# canSlaveV04.net
KiCad netlist of a schematic drawn in EAGLE
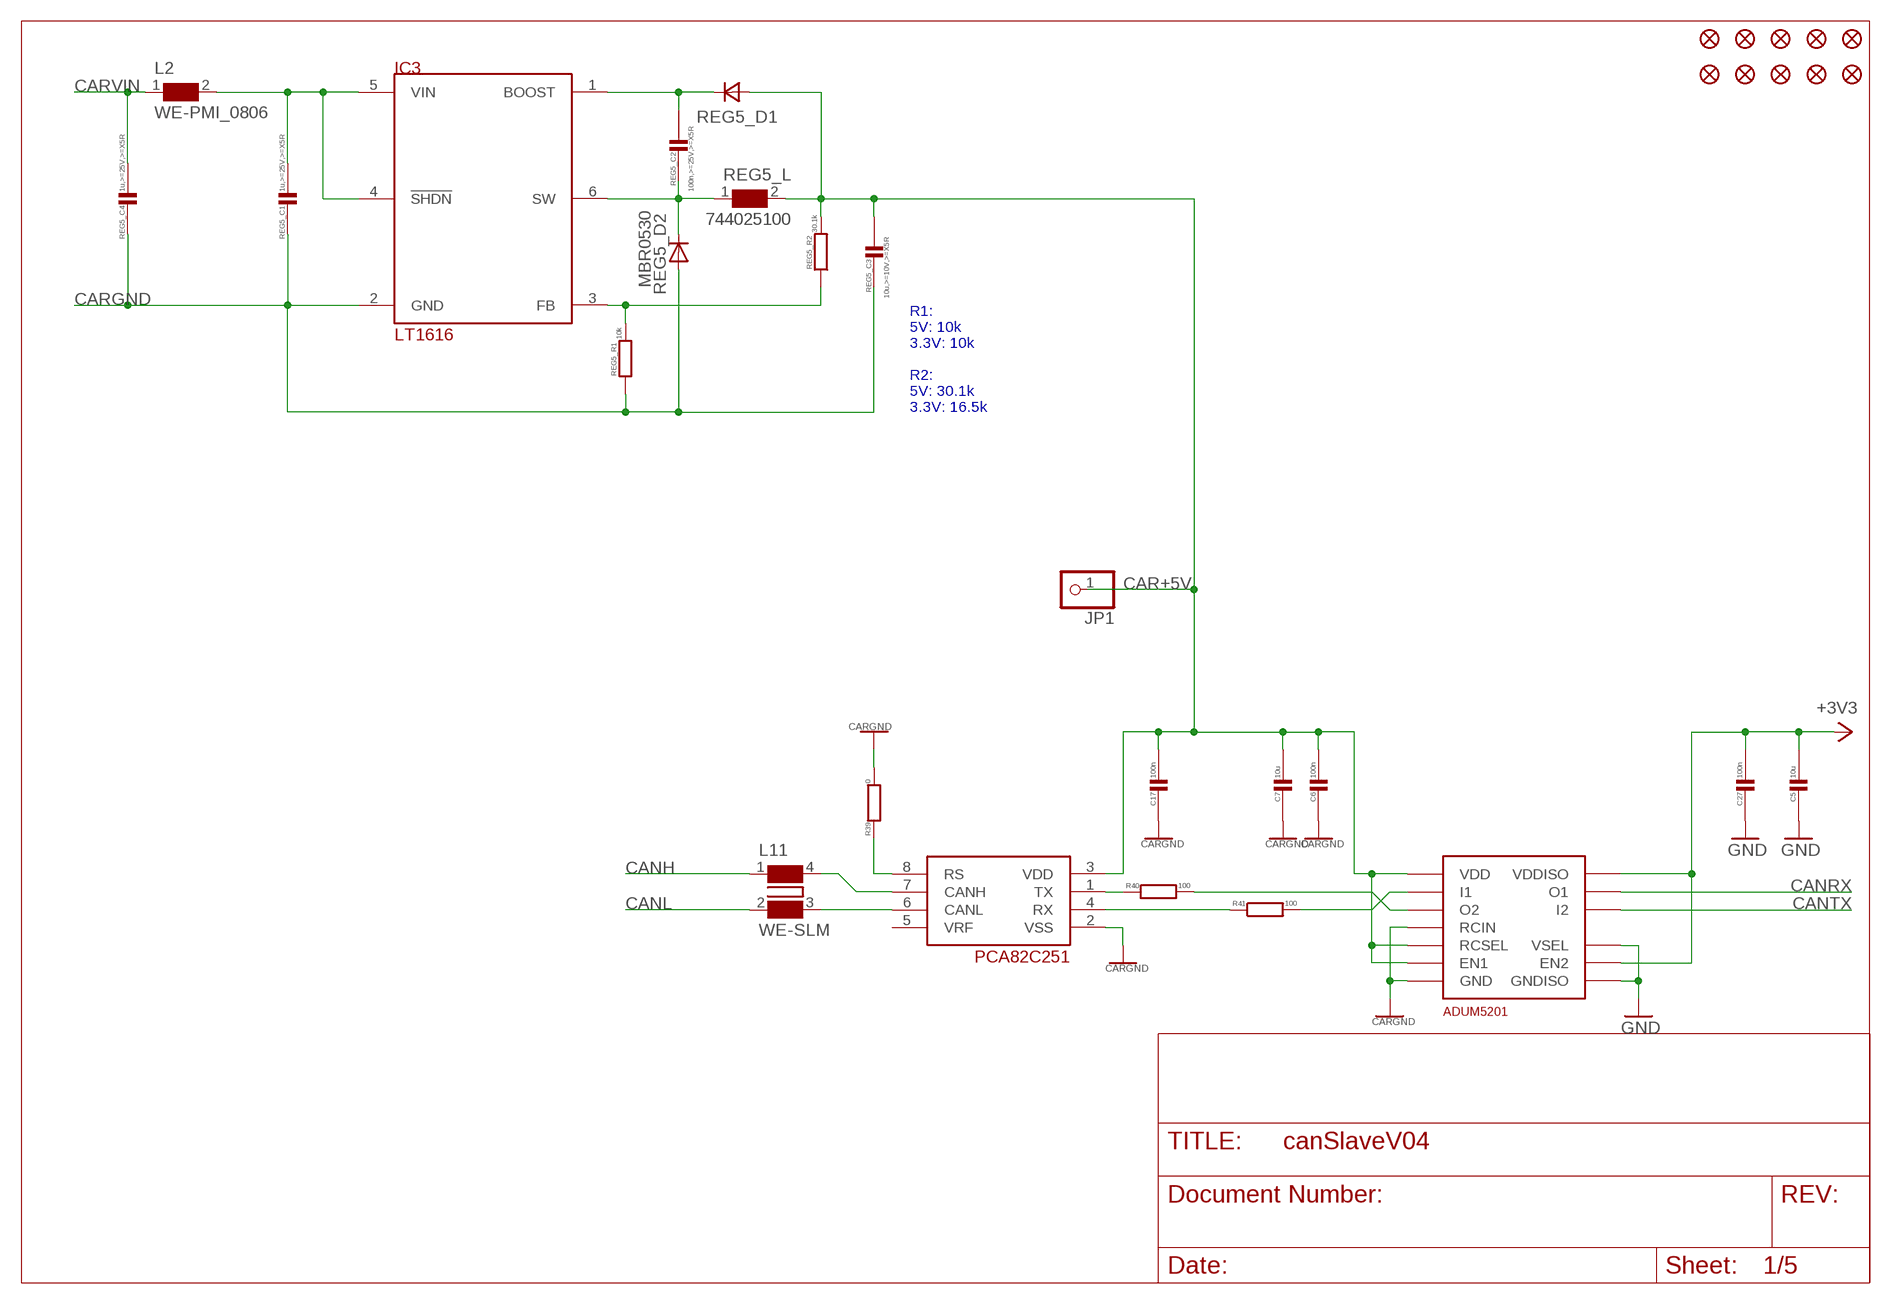
[diagram p0: schematic, sheet 1]
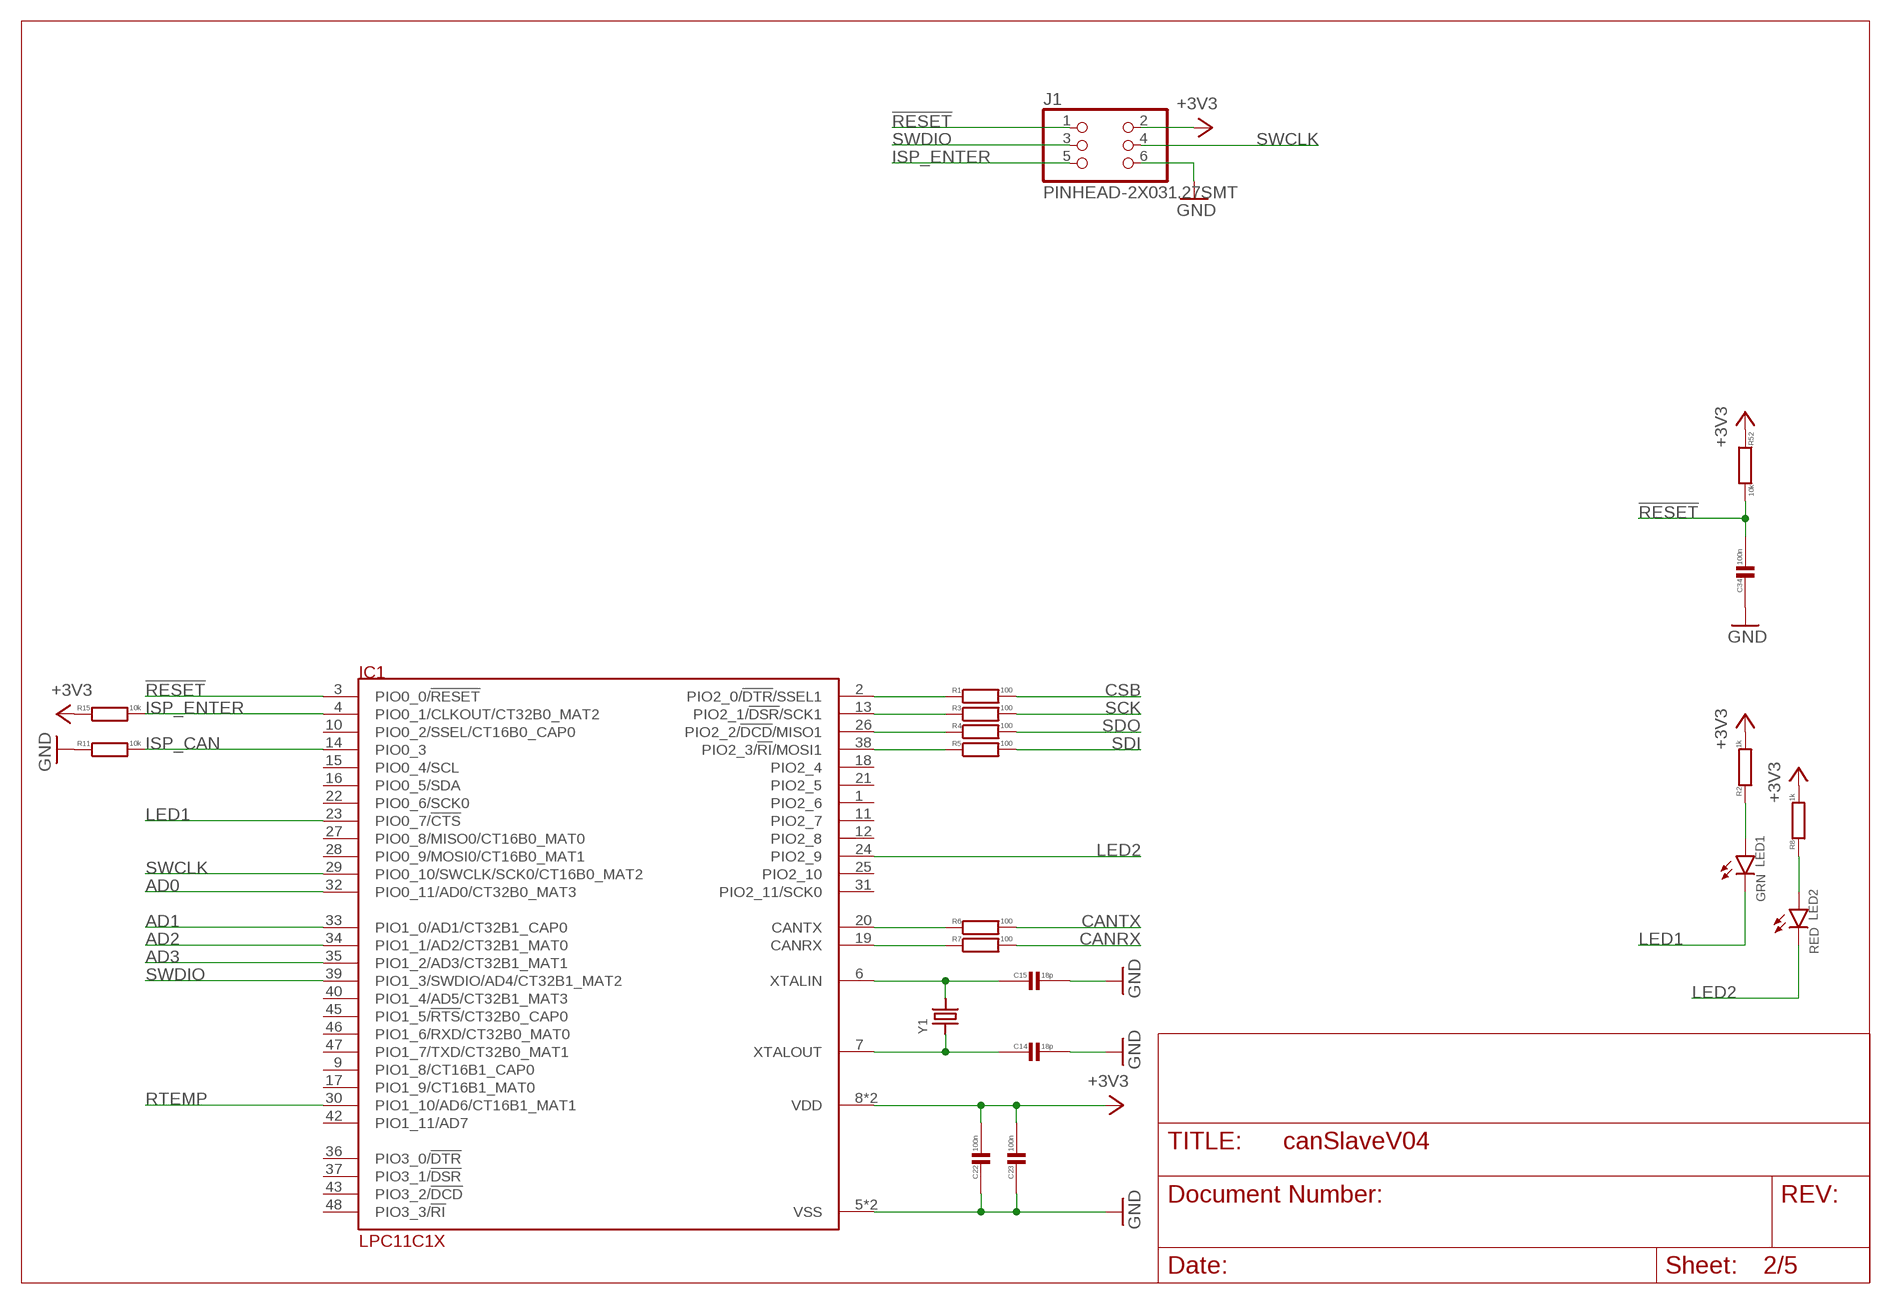
[diagram p1: schematic, sheet 2]
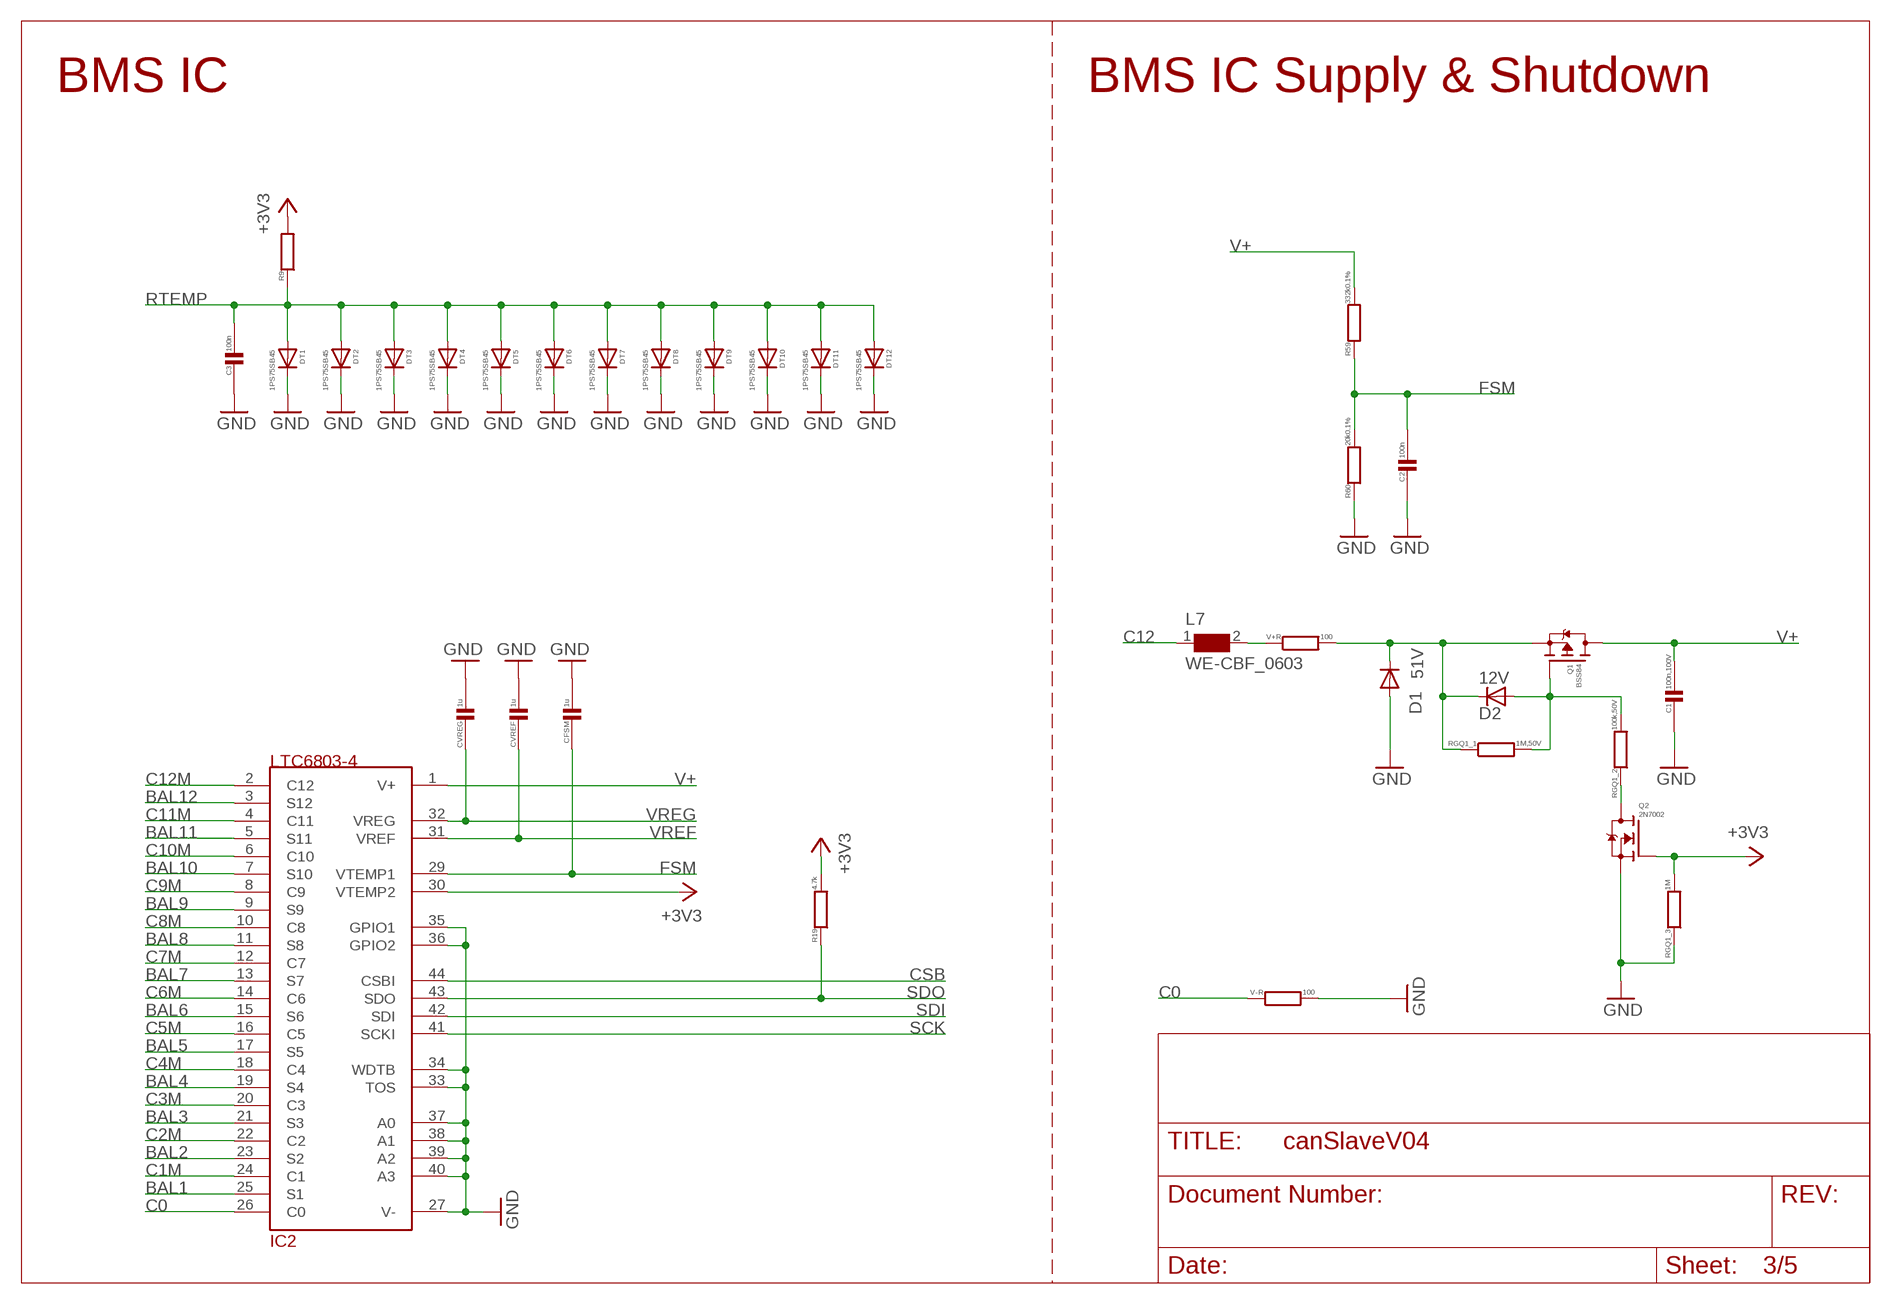
[diagram p2: schematic, sheet 3]
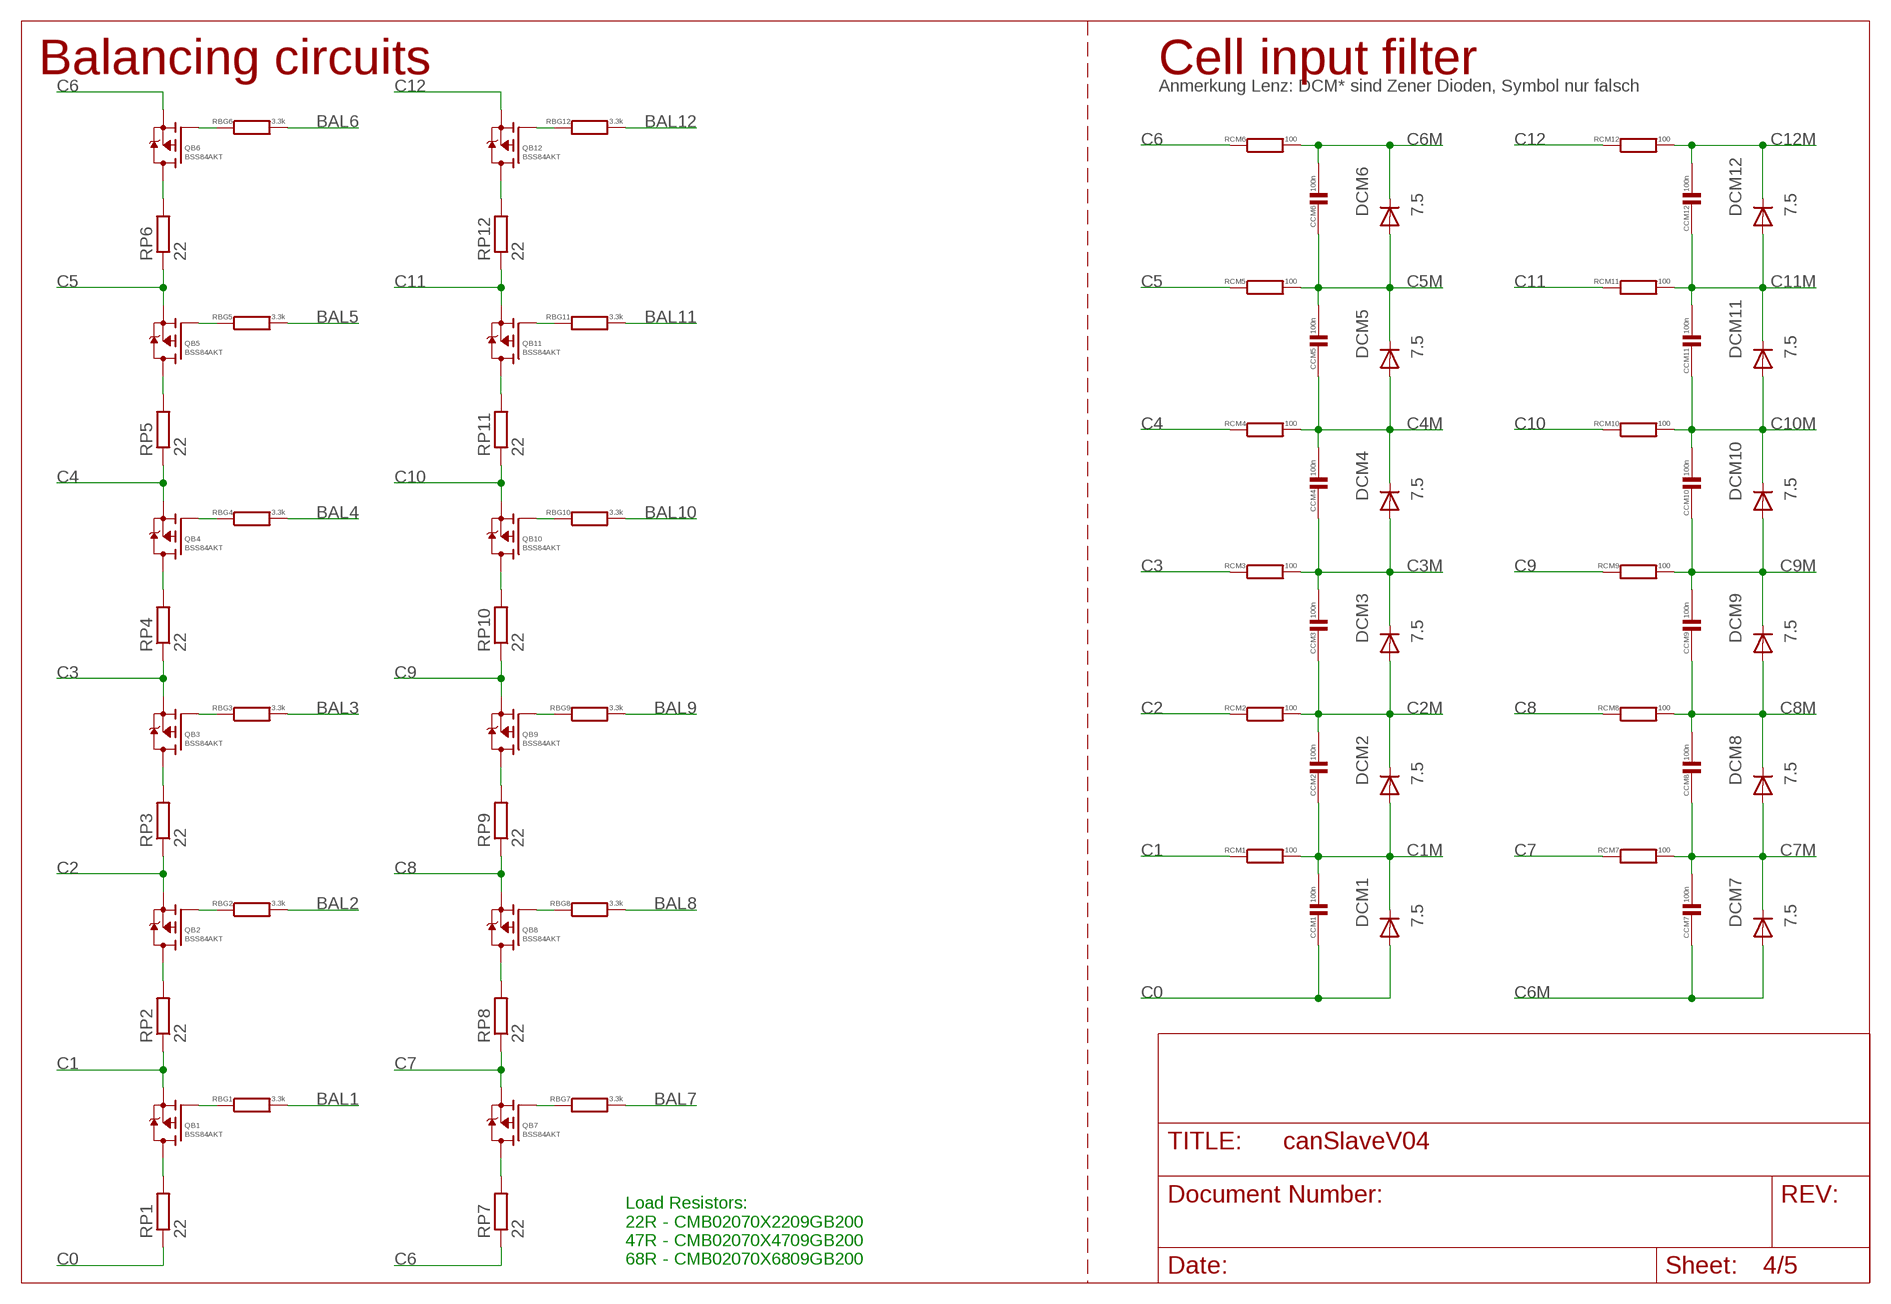
[diagram p3: schematic, sheet 4]
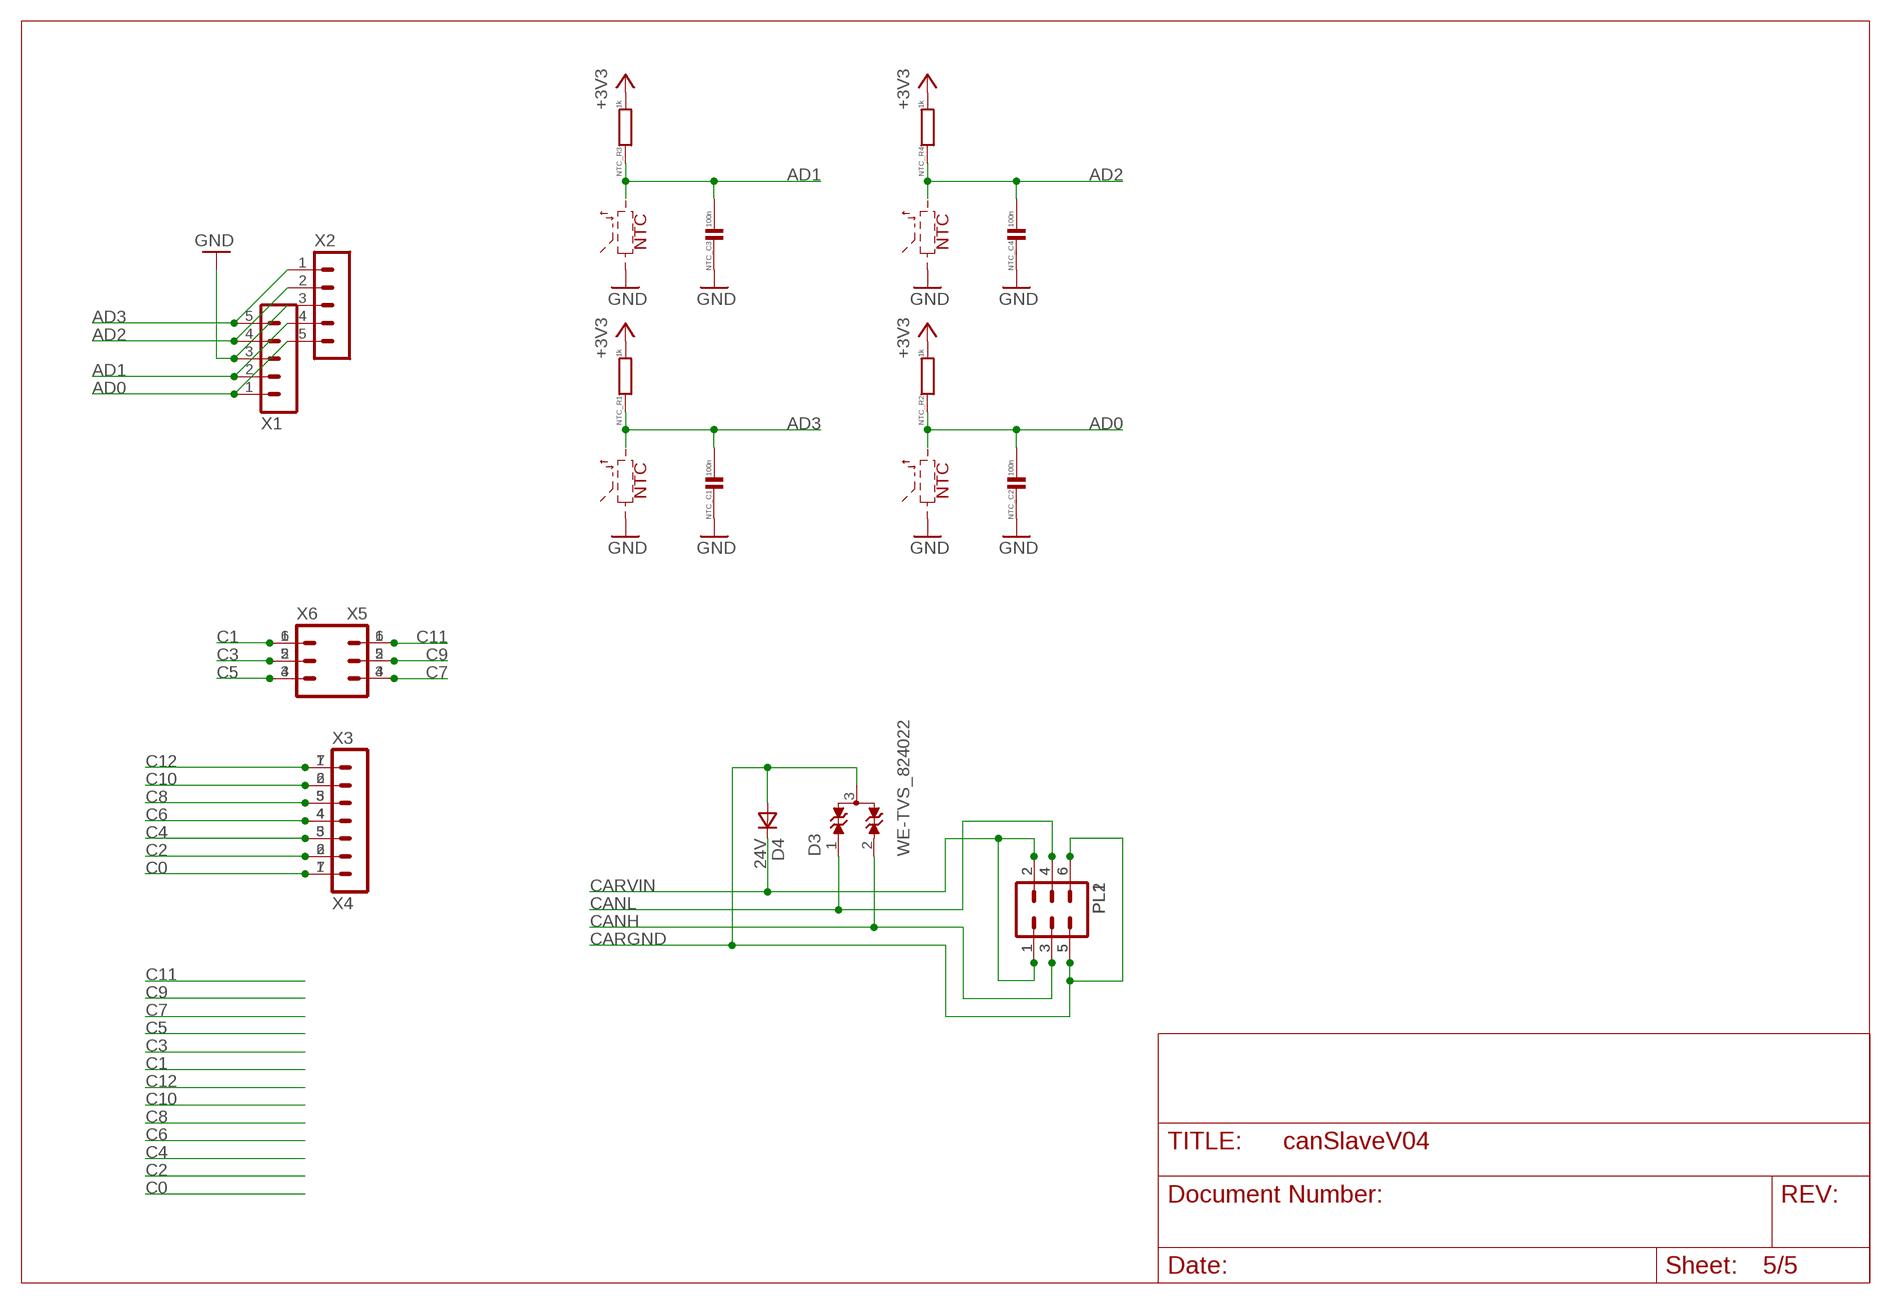
[diagram p4: schematic, sheet 5]

(export (version "E")
  (design (tool "Eeschema 10.0.6"))
  (components
    (comp (ref "D3")
      (value "WE-TVS_824022")
      (footprint "eagle-import:WE-TVS_SOT23-3L")
      (libsource (lib "eagle-import") (part "WE-TVS_824022"))
    )
    (comp (ref "D4")
      (value "24V")
      (footprint "eagle-import:SOD323")
      (fields (field (name "MPN") "CDSOD323-T05C"))
      (libsource (lib "eagle-import") (part "DSOD323"))
    )
    (comp (ref "NTC_C1")
      (value "100n")
      (footprint "eagle-import:C0402")
      (libsource (lib "eagle-import") (part "C0402"))
    )
    (comp (ref "NTC_C2")
      (value "100n")
      (footprint "eagle-import:C0402")
      (libsource (lib "eagle-import") (part "C0402"))
    )
    (comp (ref "NTC_C3")
      (value "100n")
      (footprint "eagle-import:C0402")
      (libsource (lib "eagle-import") (part "C0402"))
    )
    (comp (ref "NTC_C4")
      (value "100n")
      (footprint "eagle-import:C0402")
      (libsource (lib "eagle-import") (part "C0402"))
    )
    (comp (ref "NTC_R1")
      (value "1k")
      (footprint "eagle-import:R0402")
      (libsource (lib "eagle-import") (part "R0402"))
    )
    (comp (ref "NTC_R2")
      (value "1k")
      (footprint "eagle-import:R0402")
      (libsource (lib "eagle-import") (part "R0402"))
    )
    (comp (ref "NTC_R3")
      (value "1k")
      (footprint "eagle-import:R0402")
      (libsource (lib "eagle-import") (part "R0402"))
    )
    (comp (ref "NTC_R4")
      (value "1k")
      (footprint "eagle-import:R0402")
      (libsource (lib "eagle-import") (part "R0402"))
    )
    (comp (ref "PL1")
      (value "06V")
      (footprint "eagle-import:06V")
      (libsource (lib "eagle-import") (part "06V"))
    )
    (comp (ref "PL2")
      (value "06H")
      (footprint "eagle-import:06H")
      (libsource (lib "eagle-import") (part "06H"))
    )
    (comp (ref "X1")
      (value "HEADER_POS5_43650-0500")
      (footprint "eagle-import:43650-0500")
      (libsource (lib "eagle-import") (part "HEADER_POS5_?43650-0500"))
    )
    (comp (ref "X2")
      (value "HEADER_POS5_43650-0515")
      (footprint "eagle-import:43650-0515")
      (libsource (lib "eagle-import") (part "HEADER_POS5_?43650-0515"))
    )
    (comp (ref "X3")
      (value "HEADER_POS7_43650-0700")
      (footprint "eagle-import:43650-0700")
      (libsource (lib "eagle-import") (part "HEADER_POS7_?43650-0700"))
    )
    (comp (ref "X4")
      (value "HEADER_POS7_43650-0715")
      (footprint "eagle-import:43650-0715")
      (libsource (lib "eagle-import") (part "HEADER_POS7_?43650-0715"))
    )
    (comp (ref "X5")
      (value "HEADER_POS6_43650-0615")
      (footprint "eagle-import:43650-0615")
      (libsource (lib "eagle-import") (part "HEADER_POS6_?43650-0615"))
    )
    (comp (ref "X6")
      (value "HEADER_POS6_43650-0600")
      (footprint "eagle-import:43650-0600")
      (libsource (lib "eagle-import") (part "HEADER_POS6_?43650-0600"))
    )
    (comp (ref "C1")
      (value "100n,100V")
      (footprint "eagle-import:C0603")
      (libsource (lib "eagle-import") (part "C0603"))
    )
    (comp (ref "C2")
      (value "100n")
      (footprint "eagle-import:C0402")
      (libsource (lib "eagle-import") (part "C0402"))
    )
    (comp (ref "C3")
      (value "100n")
      (footprint "eagle-import:C0402")
      (libsource (lib "eagle-import") (part "C0402"))
    )
    (comp (ref "CFSM")
      (value "1u")
      (footprint "eagle-import:C0402")
      (libsource (lib "eagle-import") (part "C0402"))
    )
    (comp (ref "CVREF")
      (value "1u")
      (footprint "eagle-import:C0402")
      (libsource (lib "eagle-import") (part "C0402"))
    )
    (comp (ref "CVREG")
      (value "1u")
      (footprint "eagle-import:C0402")
      (libsource (lib "eagle-import") (part "C0402"))
    )
    (comp (ref "D1")
      (value "51V")
      (footprint "eagle-import:SOD323-R")
      (libsource (lib "eagle-import") (part "DIODE-SOD323-R"))
    )
    (comp (ref "D2")
      (value "12V")
      (footprint "eagle-import:SOD323-R")
      (libsource (lib "eagle-import") (part "DIODE-SOD323-R"))
    )
    (comp (ref "DT1")
      (value "1PS75SB45")
      (footprint "eagle-import:SOT416")
      (libsource (lib "eagle-import") (part "DIODE-SOT416"))
    )
    (comp (ref "DT2")
      (value "1PS75SB45")
      (footprint "eagle-import:SOT416")
      (libsource (lib "eagle-import") (part "DIODE-SOT416"))
    )
    (comp (ref "DT3")
      (value "1PS75SB45")
      (footprint "eagle-import:SOT416")
      (libsource (lib "eagle-import") (part "DIODE-SOT416"))
    )
    (comp (ref "DT4")
      (value "1PS75SB45")
      (footprint "eagle-import:SOT416")
      (libsource (lib "eagle-import") (part "DIODE-SOT416"))
    )
    (comp (ref "DT5")
      (value "1PS75SB45")
      (footprint "eagle-import:SOT416")
      (libsource (lib "eagle-import") (part "DIODE-SOT416"))
    )
    (comp (ref "DT6")
      (value "1PS75SB45")
      (footprint "eagle-import:SOT416")
      (libsource (lib "eagle-import") (part "DIODE-SOT416"))
    )
    (comp (ref "DT7")
      (value "1PS75SB45")
      (footprint "eagle-import:SOT416")
      (libsource (lib "eagle-import") (part "DIODE-SOT416"))
    )
    (comp (ref "DT8")
      (value "1PS75SB45")
      (footprint "eagle-import:SOT416")
      (libsource (lib "eagle-import") (part "DIODE-SOT416"))
    )
    (comp (ref "DT9")
      (value "1PS75SB45")
      (footprint "eagle-import:SOT416")
      (libsource (lib "eagle-import") (part "DIODE-SOT416"))
    )
    (comp (ref "DT10")
      (value "1PS75SB45")
      (footprint "eagle-import:SOT416")
      (libsource (lib "eagle-import") (part "DIODE-SOT416"))
    )
    (comp (ref "DT11")
      (value "1PS75SB45")
      (footprint "eagle-import:SOT416")
      (libsource (lib "eagle-import") (part "DIODE-SOT416"))
    )
    (comp (ref "DT12")
      (value "1PS75SB45")
      (footprint "eagle-import:SOT416")
      (libsource (lib "eagle-import") (part "DIODE-SOT416"))
    )
    (comp (ref "IC2")
      (value "LTC6803-4")
      (footprint "eagle-import:44SSOP")
      (libsource (lib "eagle-import") (part "LTC6803-4"))
    )
    (comp (ref "L7")
      (value "WE-CBF_0603")
      (footprint "eagle-import:0603")
      (libsource (lib "eagle-import") (part "WE-CBF_0603"))
    )
    (comp (ref "Q1")
      (value "BSS84")
      (footprint "eagle-import:SOT23")
      (libsource (lib "eagle-import") (part "BSS84"))
    )
    (comp (ref "Q2")
      (value "2N7002")
      (footprint "eagle-import:SOT23")
      (libsource (lib "eagle-import") (part "2N7002"))
    )
    (comp (ref "R9")
      (value "R0603")
      (footprint "eagle-import:R0603")
      (libsource (lib "eagle-import") (part "R0603"))
    )
    (comp (ref "R19")
      (value "4.7k")
      (footprint "eagle-import:R0402")
      (libsource (lib "eagle-import") (part "R0402"))
    )
    (comp (ref "R59")
      (value "332k0.1%")
      (footprint "eagle-import:R0603")
      (libsource (lib "eagle-import") (part "R0603"))
    )
    (comp (ref "R60")
      (value "20k0.1%")
      (footprint "eagle-import:R0402")
      (libsource (lib "eagle-import") (part "R0402"))
    )
    (comp (ref "RGQ1_1")
      (value "1M,50V")
      (footprint "eagle-import:R0603")
      (libsource (lib "eagle-import") (part "R0603"))
    )
    (comp (ref "RGQ1_2")
      (value "100k,50V")
      (footprint "eagle-import:R0603")
      (libsource (lib "eagle-import") (part "R0603"))
    )
    (comp (ref "RGQ1_3")
      (value "1M")
      (footprint "eagle-import:R0402")
      (libsource (lib "eagle-import") (part "R0402"))
    )
    (comp (ref "V+R")
      (value "100")
      (footprint "eagle-import:R0603")
      (libsource (lib "eagle-import") (part "R0603"))
    )
    (comp (ref "V-R")
      (value "100")
      (footprint "eagle-import:R0603")
      (libsource (lib "eagle-import") (part "R0603"))
    )
    (comp (ref "C14")
      (value "18p")
      (footprint "eagle-import:C0402")
      (libsource (lib "eagle-import") (part "C0402"))
    )
    (comp (ref "C15")
      (value "18p")
      (footprint "eagle-import:C0402")
      (libsource (lib "eagle-import") (part "C0402"))
    )
    (comp (ref "C22")
      (value "100n")
      (footprint "eagle-import:C0402")
      (libsource (lib "eagle-import") (part "C0402"))
    )
    (comp (ref "C23")
      (value "100n")
      (footprint "eagle-import:C0402")
      (libsource (lib "eagle-import") (part "C0402"))
    )
    (comp (ref "C34")
      (value "100n")
      (footprint "eagle-import:C0402")
      (libsource (lib "eagle-import") (part "C0402"))
    )
    (comp (ref "IC1")
      (value "LPC11C1X")
      (footprint "eagle-import:LQFP48")
      (libsource (lib "eagle-import") (part "LPC11C1X"))
    )
    (comp (ref "J1")
      (value "PINHEAD-2X031.27SMT")
      (footprint "eagle-import:2X03_1.27MM_SMT")
      (libsource (lib "eagle-import") (part "PINHEAD-2X031.27SMT"))
    )
    (comp (ref "LED1")
      (value "GRN")
      (footprint "eagle-import:CHIPLED_0402")
      (libsource (lib "eagle-import") (part "LED0402"))
    )
    (comp (ref "LED2")
      (value "RED")
      (footprint "eagle-import:CHIPLED_0402")
      (libsource (lib "eagle-import") (part "LED0402"))
    )
    (comp (ref "R1")
      (value "100")
      (footprint "eagle-import:R0402")
      (libsource (lib "eagle-import") (part "R0402"))
    )
    (comp (ref "R2")
      (value "1k")
      (footprint "eagle-import:R0402")
      (libsource (lib "eagle-import") (part "R0402"))
    )
    (comp (ref "R3")
      (value "100")
      (footprint "eagle-import:R0402")
      (libsource (lib "eagle-import") (part "R0402"))
    )
    (comp (ref "R4")
      (value "100")
      (footprint "eagle-import:R0402")
      (libsource (lib "eagle-import") (part "R0402"))
    )
    (comp (ref "R5")
      (value "100")
      (footprint "eagle-import:R0402")
      (libsource (lib "eagle-import") (part "R0402"))
    )
    (comp (ref "R6")
      (value "100")
      (footprint "eagle-import:R0402")
      (libsource (lib "eagle-import") (part "R0402"))
    )
    (comp (ref "R7")
      (value "100")
      (footprint "eagle-import:R0402")
      (libsource (lib "eagle-import") (part "R0402"))
    )
    (comp (ref "R8")
      (value "1k")
      (footprint "eagle-import:R0402")
      (libsource (lib "eagle-import") (part "R0402"))
    )
    (comp (ref "R11")
      (value "10k")
      (footprint "eagle-import:R0402")
      (libsource (lib "eagle-import") (part "R0402"))
    )
    (comp (ref "R15")
      (value "10k")
      (footprint "eagle-import:R0402")
      (libsource (lib "eagle-import") (part "R0402"))
    )
    (comp (ref "R52")
      (value "10k")
      (footprint "eagle-import:R0402")
      (libsource (lib "eagle-import") (part "R0402"))
    )
    (comp (ref "Y1")
      (value "CRYSTALTHIN")
      (footprint "eagle-import:CRYSTAL_3.2X2.5")
      (libsource (lib "eagle-import") (part "CRYSTALTHIN"))
    )
    (comp (ref "C5")
      (value "10u")
      (footprint "eagle-import:C0603")
      (libsource (lib "eagle-import") (part "C0603"))
    )
    (comp (ref "C6")
      (value "100n")
      (footprint "eagle-import:C0402")
      (libsource (lib "eagle-import") (part "C0402"))
    )
    (comp (ref "C7")
      (value "10u")
      (footprint "eagle-import:C0603")
      (libsource (lib "eagle-import") (part "C0603"))
    )
    (comp (ref "C17")
      (value "100n")
      (footprint "eagle-import:C0402")
      (libsource (lib "eagle-import") (part "C0402"))
    )
    (comp (ref "C27")
      (value "100n")
      (footprint "eagle-import:C0402")
      (libsource (lib "eagle-import") (part "C0402"))
    )
    (comp (ref "FID1")
      (value "FIDUCIAL\"\"")
      (footprint "eagle-import:FIDUCIAL_1MM")
      (libsource (lib "eagle-import") (part "FIDUCIAL{dblquote}{dblquote}"))
    )
    (comp (ref "FID2")
      (value "FIDUCIAL\"\"")
      (footprint "eagle-import:FIDUCIAL_1MM")
      (libsource (lib "eagle-import") (part "FIDUCIAL{dblquote}{dblquote}"))
    )
    (comp (ref "FID3")
      (value "FIDUCIAL\"\"")
      (footprint "eagle-import:FIDUCIAL_1MM")
      (libsource (lib "eagle-import") (part "FIDUCIAL{dblquote}{dblquote}"))
    )
    (comp (ref "FID4")
      (value "FIDUCIAL\"\"")
      (footprint "eagle-import:FIDUCIAL_1MM")
      (libsource (lib "eagle-import") (part "FIDUCIAL{dblquote}{dblquote}"))
    )
    (comp (ref "FID5")
      (value "FIDUCIAL\"\"")
      (footprint "eagle-import:FIDUCIAL_1MM")
      (libsource (lib "eagle-import") (part "FIDUCIAL{dblquote}{dblquote}"))
    )
    (comp (ref "FID6")
      (value "FIDUCIAL\"\"")
      (footprint "eagle-import:FIDUCIAL_1MM")
      (libsource (lib "eagle-import") (part "FIDUCIAL{dblquote}{dblquote}"))
    )
    (comp (ref "FID7")
      (value "FIDUCIAL\"\"")
      (footprint "eagle-import:FIDUCIAL_1MM")
      (libsource (lib "eagle-import") (part "FIDUCIAL{dblquote}{dblquote}"))
    )
    (comp (ref "FID8")
      (value "FIDUCIAL\"\"")
      (footprint "eagle-import:FIDUCIAL_1MM")
      (libsource (lib "eagle-import") (part "FIDUCIAL{dblquote}{dblquote}"))
    )
    (comp (ref "FID9")
      (value "FIDUCIAL\"\"")
      (footprint "eagle-import:FIDUCIAL_1MM")
      (libsource (lib "eagle-import") (part "FIDUCIAL{dblquote}{dblquote}"))
    )
    (comp (ref "FID10")
      (value "FIDUCIAL\"\"")
      (footprint "eagle-import:FIDUCIAL_1MM")
      (libsource (lib "eagle-import") (part "FIDUCIAL{dblquote}{dblquote}"))
    )
    (comp (ref "IC3")
      (value "LT1616")
      (footprint "eagle-import:SOT23-6")
      (libsource (lib "eagle-import") (part "LT1616"))
    )
    (comp (ref "IC5")
      (value "PCA82C251")
      (footprint "eagle-import:SO-8")
      (libsource (lib "eagle-import") (part "MCP2551"))
    )
    (comp (ref "JP1")
      (value "PINHD-1X1")
      (footprint "eagle-import:1X01")
      (libsource (lib "eagle-import") (part "PINHD-1X1"))
    )
    (comp (ref "L2")
      (value "WE-PMI_0806")
      (footprint "eagle-import:WE-PMI_0806")
      (libsource (lib "eagle-import") (part "WE-PMI_0806"))
    )
    (comp (ref "L11")
      (value "WE-SLM")
      (footprint "eagle-import:WE-SLM")
      (libsource (lib "eagle-import") (part "WE-SLM"))
    )
    (comp (ref "R39")
      (value "0")
      (footprint "eagle-import:R0402")
      (libsource (lib "eagle-import") (part "R0402"))
    )
    (comp (ref "R40")
      (value "100")
      (footprint "eagle-import:R0402")
      (libsource (lib "eagle-import") (part "R0402"))
    )
    (comp (ref "R41")
      (value "100")
      (footprint "eagle-import:R0402")
      (libsource (lib "eagle-import") (part "R0402"))
    )
    (comp (ref "REG5_C1")
      (value "1u,>=25V,>=X5R")
      (footprint "eagle-import:C0603")
      (libsource (lib "eagle-import") (part "C0603"))
    )
    (comp (ref "REG5_C2")
      (value "100n,>=25V,>=X5R")
      (footprint "eagle-import:C0402")
      (libsource (lib "eagle-import") (part "C0402"))
    )
    (comp (ref "REG5_C3")
      (value "10u,>=10V,>=X5R")
      (footprint "eagle-import:C0603")
      (libsource (lib "eagle-import") (part "C0603"))
    )
    (comp (ref "REG5_C4")
      (value "1u,>=25V,>=X5R")
      (footprint "eagle-import:C0603")
      (libsource (lib "eagle-import") (part "C0603"))
    )
    (comp (ref "REG5_D1")
      (value "DSOD323")
      (footprint "eagle-import:SOD323")
      (fields (field (name "MPN") "CDSOD323-T05C"))
      (libsource (lib "eagle-import") (part "DSOD323"))
    )
    (comp (ref "REG5_D2")
      (value "MBR0530")
      (footprint "eagle-import:SOD123")
      (libsource (lib "eagle-import") (part "D-SOD123"))
    )
    (comp (ref "REG5_L")
      (value "744025100")
      (footprint "eagle-import:WE-TPC_2828")
      (libsource (lib "eagle-import") (part "WE-TPC_2828"))
    )
    (comp (ref "REG5_R1")
      (value "10k")
      (footprint "eagle-import:R0402")
      (libsource (lib "eagle-import") (part "R0402"))
    )
    (comp (ref "REG5_R2")
      (value "30.1k")
      (footprint "eagle-import:R0402")
      (libsource (lib "eagle-import") (part "R0402"))
    )
    (comp (ref "U$2")
      (value "ADUM5201")
      (footprint "eagle-import:SO16WB")
      (libsource (lib "eagle-import") (part "ADUM5201"))
    )
    (comp (ref "CCM1")
      (value "100n")
      (footprint "eagle-import:C0402")
      (libsource (lib "eagle-import") (part "C0402"))
    )
    (comp (ref "CCM2")
      (value "100n")
      (footprint "eagle-import:C0402")
      (libsource (lib "eagle-import") (part "C0402"))
    )
    (comp (ref "CCM3")
      (value "100n")
      (footprint "eagle-import:C0402")
      (libsource (lib "eagle-import") (part "C0402"))
    )
    (comp (ref "CCM4")
      (value "100n")
      (footprint "eagle-import:C0402")
      (libsource (lib "eagle-import") (part "C0402"))
    )
    (comp (ref "CCM5")
      (value "100n")
      (footprint "eagle-import:C0402")
      (libsource (lib "eagle-import") (part "C0402"))
    )
    (comp (ref "CCM6")
      (value "100n")
      (footprint "eagle-import:C0402")
      (libsource (lib "eagle-import") (part "C0402"))
    )
    (comp (ref "CCM7")
      (value "100n")
      (footprint "eagle-import:C0402")
      (libsource (lib "eagle-import") (part "C0402"))
    )
    (comp (ref "CCM8")
      (value "100n")
      (footprint "eagle-import:C0402")
      (libsource (lib "eagle-import") (part "C0402"))
    )
    (comp (ref "CCM9")
      (value "100n")
      (footprint "eagle-import:C0402")
      (libsource (lib "eagle-import") (part "C0402"))
    )
    (comp (ref "CCM10")
      (value "100n")
      (footprint "eagle-import:C0402")
      (libsource (lib "eagle-import") (part "C0402"))
    )
    (comp (ref "CCM11")
      (value "100n")
      (footprint "eagle-import:C0402")
      (libsource (lib "eagle-import") (part "C0402"))
    )
    (comp (ref "CCM12")
      (value "100n")
      (footprint "eagle-import:C0402")
      (libsource (lib "eagle-import") (part "C0402"))
    )
    (comp (ref "DCM1")
      (value "7.5")
      (footprint "eagle-import:SOD323-L")
      (libsource (lib "eagle-import") (part "DIODE-SOD323-L"))
    )
    (comp (ref "DCM2")
      (value "7.5")
      (footprint "eagle-import:SOD323-L")
      (libsource (lib "eagle-import") (part "DIODE-SOD323-L"))
    )
    (comp (ref "DCM3")
      (value "7.5")
      (footprint "eagle-import:SOD323-L")
      (libsource (lib "eagle-import") (part "DIODE-SOD323-L"))
    )
    (comp (ref "DCM4")
      (value "7.5")
      (footprint "eagle-import:SOD323-L")
      (libsource (lib "eagle-import") (part "DIODE-SOD323-L"))
    )
    (comp (ref "DCM5")
      (value "7.5")
      (footprint "eagle-import:SOD323-L")
      (libsource (lib "eagle-import") (part "DIODE-SOD323-L"))
    )
    (comp (ref "DCM6")
      (value "7.5")
      (footprint "eagle-import:SOD323-L")
      (libsource (lib "eagle-import") (part "DIODE-SOD323-L"))
    )
    (comp (ref "DCM7")
      (value "7.5")
      (footprint "eagle-import:SOD323-L")
      (libsource (lib "eagle-import") (part "DIODE-SOD323-L"))
    )
    (comp (ref "DCM8")
      (value "7.5")
      (footprint "eagle-import:SOD323-L")
      (libsource (lib "eagle-import") (part "DIODE-SOD323-L"))
    )
    (comp (ref "DCM9")
      (value "7.5")
      (footprint "eagle-import:SOD323-L")
      (libsource (lib "eagle-import") (part "DIODE-SOD323-L"))
    )
    (comp (ref "DCM10")
      (value "7.5")
      (footprint "eagle-import:SOD323-L")
      (libsource (lib "eagle-import") (part "DIODE-SOD323-L"))
    )
    (comp (ref "DCM11")
      (value "7.5")
      (footprint "eagle-import:SOD323-L")
      (libsource (lib "eagle-import") (part "DIODE-SOD323-L"))
    )
    (comp (ref "DCM12")
      (value "7.5")
      (footprint "eagle-import:SOD323-L")
      (libsource (lib "eagle-import") (part "DIODE-SOD323-L"))
    )
    (comp (ref "QB1")
      (value "BSS84AKT")
      (footprint "eagle-import:SOT416")
      (libsource (lib "eagle-import") (part "BSS84AKT"))
    )
    (comp (ref "QB2")
      (value "BSS84AKT")
      (footprint "eagle-import:SOT416")
      (libsource (lib "eagle-import") (part "BSS84AKT"))
    )
    (comp (ref "QB3")
      (value "BSS84AKT")
      (footprint "eagle-import:SOT416")
      (libsource (lib "eagle-import") (part "BSS84AKT"))
    )
    (comp (ref "QB4")
      (value "BSS84AKT")
      (footprint "eagle-import:SOT416")
      (libsource (lib "eagle-import") (part "BSS84AKT"))
    )
    (comp (ref "QB5")
      (value "BSS84AKT")
      (footprint "eagle-import:SOT416")
      (libsource (lib "eagle-import") (part "BSS84AKT"))
    )
    (comp (ref "QB6")
      (value "BSS84AKT")
      (footprint "eagle-import:SOT416")
      (libsource (lib "eagle-import") (part "BSS84AKT"))
    )
    (comp (ref "QB7")
      (value "BSS84AKT")
      (footprint "eagle-import:SOT416")
      (libsource (lib "eagle-import") (part "BSS84AKT"))
    )
    (comp (ref "QB8")
      (value "BSS84AKT")
      (footprint "eagle-import:SOT416")
      (libsource (lib "eagle-import") (part "BSS84AKT"))
    )
    (comp (ref "QB9")
      (value "BSS84AKT")
      (footprint "eagle-import:SOT416")
      (libsource (lib "eagle-import") (part "BSS84AKT"))
    )
    (comp (ref "QB10")
      (value "BSS84AKT")
      (footprint "eagle-import:SOT416")
      (libsource (lib "eagle-import") (part "BSS84AKT"))
    )
    (comp (ref "QB11")
      (value "BSS84AKT")
      (footprint "eagle-import:SOT416")
      (libsource (lib "eagle-import") (part "BSS84AKT"))
    )
    (comp (ref "QB12")
      (value "BSS84AKT")
      (footprint "eagle-import:SOT416")
      (libsource (lib "eagle-import") (part "BSS84AKT"))
    )
    (comp (ref "RBG1")
      (value "3.3k")
      (footprint "eagle-import:R0402")
      (libsource (lib "eagle-import") (part "R0402"))
    )
    (comp (ref "RBG2")
      (value "3.3k")
      (footprint "eagle-import:R0402")
      (libsource (lib "eagle-import") (part "R0402"))
    )
    (comp (ref "RBG3")
      (value "3.3k")
      (footprint "eagle-import:R0402")
      (libsource (lib "eagle-import") (part "R0402"))
    )
    (comp (ref "RBG4")
      (value "3.3k")
      (footprint "eagle-import:R0402")
      (libsource (lib "eagle-import") (part "R0402"))
    )
    (comp (ref "RBG5")
      (value "3.3k")
      (footprint "eagle-import:R0402")
      (libsource (lib "eagle-import") (part "R0402"))
    )
    (comp (ref "RBG6")
      (value "3.3k")
      (footprint "eagle-import:R0402")
      (libsource (lib "eagle-import") (part "R0402"))
    )
    (comp (ref "RBG7")
      (value "3.3k")
      (footprint "eagle-import:R0402")
      (libsource (lib "eagle-import") (part "R0402"))
    )
    (comp (ref "RBG8")
      (value "3.3k")
      (footprint "eagle-import:R0402")
      (libsource (lib "eagle-import") (part "R0402"))
    )
    (comp (ref "RBG9")
      (value "3.3k")
      (footprint "eagle-import:R0402")
      (libsource (lib "eagle-import") (part "R0402"))
    )
    (comp (ref "RBG10")
      (value "3.3k")
      (footprint "eagle-import:R0402")
      (libsource (lib "eagle-import") (part "R0402"))
    )
    (comp (ref "RBG11")
      (value "3.3k")
      (footprint "eagle-import:R0402")
      (libsource (lib "eagle-import") (part "R0402"))
    )
    (comp (ref "RBG12")
      (value "3.3k")
      (footprint "eagle-import:R0402")
      (libsource (lib "eagle-import") (part "R0402"))
    )
    (comp (ref "RCM1")
      (value "100")
      (footprint "eagle-import:R0402")
      (libsource (lib "eagle-import") (part "R0402"))
    )
    (comp (ref "RCM2")
      (value "100")
      (footprint "eagle-import:R0402")
      (libsource (lib "eagle-import") (part "R0402"))
    )
    (comp (ref "RCM3")
      (value "100")
      (footprint "eagle-import:R0402")
      (libsource (lib "eagle-import") (part "R0402"))
    )
    (comp (ref "RCM4")
      (value "100")
      (footprint "eagle-import:R0402")
      (libsource (lib "eagle-import") (part "R0402"))
    )
    (comp (ref "RCM5")
      (value "100")
      (footprint "eagle-import:R0402")
      (libsource (lib "eagle-import") (part "R0402"))
    )
    (comp (ref "RCM6")
      (value "100")
      (footprint "eagle-import:R0402")
      (libsource (lib "eagle-import") (part "R0402"))
    )
    (comp (ref "RCM7")
      (value "100")
      (footprint "eagle-import:R0402")
      (libsource (lib "eagle-import") (part "R0402"))
    )
    (comp (ref "RCM8")
      (value "100")
      (footprint "eagle-import:R0402")
      (libsource (lib "eagle-import") (part "R0402"))
    )
    (comp (ref "RCM9")
      (value "100")
      (footprint "eagle-import:R0402")
      (libsource (lib "eagle-import") (part "R0402"))
    )
    (comp (ref "RCM10")
      (value "100")
      (footprint "eagle-import:R0402")
      (libsource (lib "eagle-import") (part "R0402"))
    )
    (comp (ref "RCM11")
      (value "100")
      (footprint "eagle-import:R0402")
      (libsource (lib "eagle-import") (part "R0402"))
    )
    (comp (ref "RCM12")
      (value "100")
      (footprint "eagle-import:R0402")
      (libsource (lib "eagle-import") (part "R0402"))
    )
    (comp (ref "RP1")
      (value "22")
      (footprint "eagle-import:MINI_MELF-0207R")
      (libsource (lib "eagle-import") (part "R-EU_MELF0207R"))
    )
    (comp (ref "RP2")
      (value "22")
      (footprint "eagle-import:MINI_MELF-0207R")
      (libsource (lib "eagle-import") (part "R-EU_MELF0207R"))
    )
    (comp (ref "RP3")
      (value "22")
      (footprint "eagle-import:MINI_MELF-0207R")
      (libsource (lib "eagle-import") (part "R-EU_MELF0207R"))
    )
    (comp (ref "RP4")
      (value "22")
      (footprint "eagle-import:MINI_MELF-0207R")
      (libsource (lib "eagle-import") (part "R-EU_MELF0207R"))
    )
    (comp (ref "RP5")
      (value "22")
      (footprint "eagle-import:MINI_MELF-0207R")
      (libsource (lib "eagle-import") (part "R-EU_MELF0207R"))
    )
    (comp (ref "RP6")
      (value "22")
      (footprint "eagle-import:MINI_MELF-0207R")
      (libsource (lib "eagle-import") (part "R-EU_MELF0207R"))
    )
    (comp (ref "RP7")
      (value "22")
      (footprint "eagle-import:MINI_MELF-0207R")
      (libsource (lib "eagle-import") (part "R-EU_MELF0207R"))
    )
    (comp (ref "RP8")
      (value "22")
      (footprint "eagle-import:MINI_MELF-0207R")
      (libsource (lib "eagle-import") (part "R-EU_MELF0207R"))
    )
    (comp (ref "RP9")
      (value "22")
      (footprint "eagle-import:MINI_MELF-0207R")
      (libsource (lib "eagle-import") (part "R-EU_MELF0207R"))
    )
    (comp (ref "RP10")
      (value "22")
      (footprint "eagle-import:MINI_MELF-0207R")
      (libsource (lib "eagle-import") (part "R-EU_MELF0207R"))
    )
    (comp (ref "RP11")
      (value "22")
      (footprint "eagle-import:MINI_MELF-0207R")
      (libsource (lib "eagle-import") (part "R-EU_MELF0207R"))
    )
    (comp (ref "RP12")
      (value "22")
      (footprint "eagle-import:MINI_MELF-0207R")
      (libsource (lib "eagle-import") (part "R-EU_MELF0207R"))
    )
  )
  (nets
    (net (code "1") (name "+3V3") (class "Default")
      (node (ref "C22") (pin "1") (pinfunction "1_1") (pintype "passive"))
      (node (ref "C23") (pin "1") (pinfunction "1_1") (pintype "passive"))
      (node (ref "C27") (pin "1") (pinfunction "1_1") (pintype "passive"))
      (node (ref "C5") (pin "1") (pinfunction "1_1") (pintype "passive"))
      (node (ref "IC1") (pin "44") (pinfunction "VDD_44") (pintype "bidirectional"))
      (node (ref "IC1") (pin "8") (pinfunction "VDD_8") (pintype "bidirectional"))
      (node (ref "IC2") (pin "30") (pinfunction "VTEMP2_30") (pintype "bidirectional"))
      (node (ref "J1") (pin "2") (pinfunction "2_2") (pintype "passive"))
      (node (ref "NTC_R1") (pin "2") (pinfunction "2_2") (pintype "passive"))
      (node (ref "NTC_R2") (pin "2") (pinfunction "2_2") (pintype "passive"))
      (node (ref "NTC_R3") (pin "2") (pinfunction "2_2") (pintype "passive"))
      (node (ref "NTC_R4") (pin "2") (pinfunction "2_2") (pintype "passive"))
      (node (ref "Q2") (pin "1") (pinfunction "G_1") (pintype "passive"))
      (node (ref "R15") (pin "1") (pinfunction "1_1") (pintype "passive"))
      (node (ref "R19") (pin "2") (pinfunction "2_2") (pintype "passive"))
      (node (ref "R2") (pin "2") (pinfunction "2_2") (pintype "passive"))
      (node (ref "R52") (pin "1") (pinfunction "1_1") (pintype "passive"))
      (node (ref "R8") (pin "2") (pinfunction "2_2") (pintype "passive"))
      (node (ref "R9") (pin "2") (pinfunction "2_2") (pintype "passive"))
      (node (ref "RGQ1_3") (pin "2") (pinfunction "2_2") (pintype "passive"))
      (node (ref "U$2") (pin "P$10") (pinfunction "EN2_P$10") (pintype "bidirectional"))
      (node (ref "U$2") (pin "P$16") (pinfunction "VDDISO_P$16") (pintype "bidirectional"))
    )
    (net (code "2") (name "AD0") (class "Default")
      (node (ref "IC1") (pin "32") (pinfunction "PIO0_11/AD0/CT32B0_MAT3_32") (pintype "bidirectional"))
      (node (ref "NTC_C2") (pin "1") (pinfunction "1_1") (pintype "passive"))
      (node (ref "NTC_R2") (pin "1") (pinfunction "1_1") (pintype "passive"))
      (node (ref "X1") (pin "1") (pinfunction "1_1") (pintype "passive"))
      (node (ref "X2") (pin "5") (pinfunction "5_5") (pintype "passive"))
    )
    (net (code "3") (name "AD1") (class "Default")
      (node (ref "IC1") (pin "33") (pinfunction "PIO1_0/AD1/CT32B1_CAP0_33") (pintype "bidirectional"))
      (node (ref "NTC_C3") (pin "1") (pinfunction "1_1") (pintype "passive"))
      (node (ref "NTC_R3") (pin "1") (pinfunction "1_1") (pintype "passive"))
      (node (ref "X1") (pin "2") (pinfunction "2_2") (pintype "passive"))
      (node (ref "X2") (pin "4") (pinfunction "4_4") (pintype "passive"))
    )
    (net (code "4") (name "AD2") (class "Default")
      (node (ref "IC1") (pin "34") (pinfunction "PIO1_1/AD2/CT32B1_MAT0_34") (pintype "bidirectional"))
      (node (ref "NTC_C4") (pin "1") (pinfunction "1_1") (pintype "passive"))
      (node (ref "NTC_R4") (pin "1") (pinfunction "1_1") (pintype "passive"))
      (node (ref "X1") (pin "4") (pinfunction "4_4") (pintype "passive"))
      (node (ref "X2") (pin "2") (pinfunction "2_2") (pintype "passive"))
    )
    (net (code "5") (name "AD3") (class "Default")
      (node (ref "IC1") (pin "35") (pinfunction "PIO1_2/AD3/CT32B1_MAT1_35") (pintype "bidirectional"))
      (node (ref "NTC_C1") (pin "1") (pinfunction "1_1") (pintype "passive"))
      (node (ref "NTC_R1") (pin "1") (pinfunction "1_1") (pintype "passive"))
      (node (ref "X1") (pin "5") (pinfunction "5_5") (pintype "passive"))
      (node (ref "X2") (pin "1") (pinfunction "1_1") (pintype "passive"))
    )
    (net (code "6") (name "BAL1") (class "Default")
      (node (ref "IC2") (pin "25") (pinfunction "S1_25") (pintype "bidirectional"))
      (node (ref "RBG1") (pin "2") (pinfunction "2_2") (pintype "passive"))
    )
    (net (code "7") (name "BAL2") (class "Default")
      (node (ref "IC2") (pin "23") (pinfunction "S2_23") (pintype "bidirectional"))
      (node (ref "RBG2") (pin "2") (pinfunction "2_2") (pintype "passive"))
    )
    (net (code "8") (name "BAL3") (class "Default")
      (node (ref "IC2") (pin "21") (pinfunction "S3_21") (pintype "bidirectional"))
      (node (ref "RBG3") (pin "2") (pinfunction "2_2") (pintype "passive"))
    )
    (net (code "9") (name "BAL4") (class "Default")
      (node (ref "IC2") (pin "19") (pinfunction "S4_19") (pintype "bidirectional"))
      (node (ref "RBG4") (pin "2") (pinfunction "2_2") (pintype "passive"))
    )
    (net (code "10") (name "BAL5") (class "Default")
      (node (ref "IC2") (pin "17") (pinfunction "S5_17") (pintype "bidirectional"))
      (node (ref "RBG5") (pin "2") (pinfunction "2_2") (pintype "passive"))
    )
    (net (code "11") (name "BAL6") (class "Default")
      (node (ref "IC2") (pin "15") (pinfunction "S6_15") (pintype "bidirectional"))
      (node (ref "RBG6") (pin "2") (pinfunction "2_2") (pintype "passive"))
    )
    (net (code "12") (name "BAL7") (class "Default")
      (node (ref "IC2") (pin "13") (pinfunction "S7_13") (pintype "bidirectional"))
      (node (ref "RBG7") (pin "2") (pinfunction "2_2") (pintype "passive"))
    )
    (net (code "13") (name "BAL8") (class "Default")
      (node (ref "IC2") (pin "11") (pinfunction "S8_11") (pintype "bidirectional"))
      (node (ref "RBG8") (pin "2") (pinfunction "2_2") (pintype "passive"))
    )
    (net (code "14") (name "BAL9") (class "Default")
      (node (ref "IC2") (pin "9") (pinfunction "S9_9") (pintype "bidirectional"))
      (node (ref "RBG9") (pin "2") (pinfunction "2_2") (pintype "passive"))
    )
    (net (code "15") (name "BAL10") (class "Default")
      (node (ref "IC2") (pin "7") (pinfunction "S10_7") (pintype "bidirectional"))
      (node (ref "RBG10") (pin "2") (pinfunction "2_2") (pintype "passive"))
    )
    (net (code "16") (name "BAL11") (class "Default")
      (node (ref "IC2") (pin "5") (pinfunction "S11_5") (pintype "bidirectional"))
      (node (ref "RBG11") (pin "2") (pinfunction "2_2") (pintype "passive"))
    )
    (net (code "17") (name "BAL12") (class "Default")
      (node (ref "IC2") (pin "3") (pinfunction "S12_3") (pintype "bidirectional"))
      (node (ref "RBG12") (pin "2") (pinfunction "2_2") (pintype "passive"))
    )
    (net (code "18") (name "C0") (class "Default")
      (node (ref "CCM1") (pin "2") (pinfunction "2_2") (pintype "passive"))
      (node (ref "DCM1") (pin "A") (pinfunction "A_A") (pintype "passive"))
      (node (ref "IC2") (pin "26") (pinfunction "C0_26") (pintype "bidirectional"))
      (node (ref "RP1") (pin "1") (pinfunction "1_1") (pintype "passive"))
      (node (ref "V-R") (pin "1") (pinfunction "1_1") (pintype "passive"))
      (node (ref "X3") (pin "7") (pinfunction "7_7") (pintype "passive"))
      (node (ref "X4") (pin "1") (pinfunction "1_1") (pintype "passive"))
    )
    (net (code "19") (name "C1") (class "Default")
      (node (ref "QB1") (pin "2") (pinfunction "S_2") (pintype "passive"))
      (node (ref "RCM1") (pin "1") (pinfunction "1_1") (pintype "passive"))
      (node (ref "RP2") (pin "1") (pinfunction "1_1") (pintype "passive"))
      (node (ref "X5") (pin "6") (pinfunction "6_6") (pintype "passive"))
      (node (ref "X6") (pin "1") (pinfunction "1_1") (pintype "passive"))
    )
    (net (code "20") (name "C1M") (class "Default")
      (node (ref "CCM1") (pin "1") (pinfunction "1_1") (pintype "passive"))
      (node (ref "CCM2") (pin "2") (pinfunction "2_2") (pintype "passive"))
      (node (ref "DCM1") (pin "C") (pinfunction "C_C") (pintype "passive"))
      (node (ref "DCM2") (pin "A") (pinfunction "A_A") (pintype "passive"))
      (node (ref "IC2") (pin "24") (pinfunction "C1_24") (pintype "bidirectional"))
      (node (ref "RCM1") (pin "2") (pinfunction "2_2") (pintype "passive"))
    )
    (net (code "21") (name "C2") (class "Default")
      (node (ref "QB2") (pin "2") (pinfunction "S_2") (pintype "passive"))
      (node (ref "RCM2") (pin "1") (pinfunction "1_1") (pintype "passive"))
      (node (ref "RP3") (pin "1") (pinfunction "1_1") (pintype "passive"))
      (node (ref "X3") (pin "6") (pinfunction "6_6") (pintype "passive"))
      (node (ref "X4") (pin "2") (pinfunction "2_2") (pintype "passive"))
    )
    (net (code "22") (name "C2M") (class "Default")
      (node (ref "CCM2") (pin "1") (pinfunction "1_1") (pintype "passive"))
      (node (ref "CCM3") (pin "2") (pinfunction "2_2") (pintype "passive"))
      (node (ref "DCM2") (pin "C") (pinfunction "C_C") (pintype "passive"))
      (node (ref "DCM3") (pin "A") (pinfunction "A_A") (pintype "passive"))
      (node (ref "IC2") (pin "22") (pinfunction "C2_22") (pintype "bidirectional"))
      (node (ref "RCM2") (pin "2") (pinfunction "2_2") (pintype "passive"))
    )
    (net (code "23") (name "C3") (class "Default")
      (node (ref "QB3") (pin "2") (pinfunction "S_2") (pintype "passive"))
      (node (ref "RCM3") (pin "1") (pinfunction "1_1") (pintype "passive"))
      (node (ref "RP4") (pin "1") (pinfunction "1_1") (pintype "passive"))
      (node (ref "X5") (pin "5") (pinfunction "5_5") (pintype "passive"))
      (node (ref "X6") (pin "2") (pinfunction "2_2") (pintype "passive"))
    )
    (net (code "24") (name "C3M") (class "Default")
      (node (ref "CCM3") (pin "1") (pinfunction "1_1") (pintype "passive"))
      (node (ref "CCM4") (pin "2") (pinfunction "2_2") (pintype "passive"))
      (node (ref "DCM3") (pin "C") (pinfunction "C_C") (pintype "passive"))
      (node (ref "DCM4") (pin "A") (pinfunction "A_A") (pintype "passive"))
      (node (ref "IC2") (pin "20") (pinfunction "C3_20") (pintype "bidirectional"))
      (node (ref "RCM3") (pin "2") (pinfunction "2_2") (pintype "passive"))
    )
    (net (code "25") (name "C4") (class "Default")
      (node (ref "QB4") (pin "2") (pinfunction "S_2") (pintype "passive"))
      (node (ref "RCM4") (pin "1") (pinfunction "1_1") (pintype "passive"))
      (node (ref "RP5") (pin "1") (pinfunction "1_1") (pintype "passive"))
      (node (ref "X3") (pin "5") (pinfunction "5_5") (pintype "passive"))
      (node (ref "X4") (pin "3") (pinfunction "3_3") (pintype "passive"))
    )
    (net (code "26") (name "C4M") (class "Default")
      (node (ref "CCM4") (pin "1") (pinfunction "1_1") (pintype "passive"))
      (node (ref "CCM5") (pin "2") (pinfunction "2_2") (pintype "passive"))
      (node (ref "DCM4") (pin "C") (pinfunction "C_C") (pintype "passive"))
      (node (ref "DCM5") (pin "A") (pinfunction "A_A") (pintype "passive"))
      (node (ref "IC2") (pin "18") (pinfunction "C4_18") (pintype "bidirectional"))
      (node (ref "RCM4") (pin "2") (pinfunction "2_2") (pintype "passive"))
    )
    (net (code "27") (name "C5") (class "Default")
      (node (ref "QB5") (pin "2") (pinfunction "S_2") (pintype "passive"))
      (node (ref "RCM5") (pin "1") (pinfunction "1_1") (pintype "passive"))
      (node (ref "RP6") (pin "1") (pinfunction "1_1") (pintype "passive"))
      (node (ref "X5") (pin "4") (pinfunction "4_4") (pintype "passive"))
      (node (ref "X6") (pin "3") (pinfunction "3_3") (pintype "passive"))
    )
    (net (code "28") (name "C5M") (class "Default")
      (node (ref "CCM5") (pin "1") (pinfunction "1_1") (pintype "passive"))
      (node (ref "CCM6") (pin "2") (pinfunction "2_2") (pintype "passive"))
      (node (ref "DCM5") (pin "C") (pinfunction "C_C") (pintype "passive"))
      (node (ref "DCM6") (pin "A") (pinfunction "A_A") (pintype "passive"))
      (node (ref "IC2") (pin "16") (pinfunction "C5_16") (pintype "bidirectional"))
      (node (ref "RCM5") (pin "2") (pinfunction "2_2") (pintype "passive"))
    )
    (net (code "29") (name "C6") (class "Default")
      (node (ref "QB6") (pin "2") (pinfunction "S_2") (pintype "passive"))
      (node (ref "RCM6") (pin "1") (pinfunction "1_1") (pintype "passive"))
      (node (ref "RP7") (pin "1") (pinfunction "1_1") (pintype "passive"))
      (node (ref "X3") (pin "4") (pinfunction "4_4") (pintype "passive"))
      (node (ref "X4") (pin "4") (pinfunction "4_4") (pintype "passive"))
    )
    (net (code "30") (name "C6M") (class "Default")
      (node (ref "CCM6") (pin "1") (pinfunction "1_1") (pintype "passive"))
      (node (ref "CCM7") (pin "2") (pinfunction "2_2") (pintype "passive"))
      (node (ref "DCM6") (pin "C") (pinfunction "C_C") (pintype "passive"))
      (node (ref "DCM7") (pin "A") (pinfunction "A_A") (pintype "passive"))
      (node (ref "IC2") (pin "14") (pinfunction "C6_14") (pintype "bidirectional"))
      (node (ref "RCM6") (pin "2") (pinfunction "2_2") (pintype "passive"))
    )
    (net (code "31") (name "C7") (class "Default")
      (node (ref "QB7") (pin "2") (pinfunction "S_2") (pintype "passive"))
      (node (ref "RCM7") (pin "1") (pinfunction "1_1") (pintype "passive"))
      (node (ref "RP8") (pin "1") (pinfunction "1_1") (pintype "passive"))
      (node (ref "X5") (pin "3") (pinfunction "3_3") (pintype "passive"))
      (node (ref "X6") (pin "4") (pinfunction "4_4") (pintype "passive"))
    )
    (net (code "32") (name "C7M") (class "Default")
      (node (ref "CCM7") (pin "1") (pinfunction "1_1") (pintype "passive"))
      (node (ref "CCM8") (pin "2") (pinfunction "2_2") (pintype "passive"))
      (node (ref "DCM7") (pin "C") (pinfunction "C_C") (pintype "passive"))
      (node (ref "DCM8") (pin "A") (pinfunction "A_A") (pintype "passive"))
      (node (ref "IC2") (pin "12") (pinfunction "C7_12") (pintype "bidirectional"))
      (node (ref "RCM7") (pin "2") (pinfunction "2_2") (pintype "passive"))
    )
    (net (code "33") (name "C8") (class "Default")
      (node (ref "QB8") (pin "2") (pinfunction "S_2") (pintype "passive"))
      (node (ref "RCM8") (pin "1") (pinfunction "1_1") (pintype "passive"))
      (node (ref "RP9") (pin "1") (pinfunction "1_1") (pintype "passive"))
      (node (ref "X3") (pin "3") (pinfunction "3_3") (pintype "passive"))
      (node (ref "X4") (pin "5") (pinfunction "5_5") (pintype "passive"))
    )
    (net (code "34") (name "C8M") (class "Default")
      (node (ref "CCM8") (pin "1") (pinfunction "1_1") (pintype "passive"))
      (node (ref "CCM9") (pin "2") (pinfunction "2_2") (pintype "passive"))
      (node (ref "DCM8") (pin "C") (pinfunction "C_C") (pintype "passive"))
      (node (ref "DCM9") (pin "A") (pinfunction "A_A") (pintype "passive"))
      (node (ref "IC2") (pin "10") (pinfunction "C8_10") (pintype "bidirectional"))
      (node (ref "RCM8") (pin "2") (pinfunction "2_2") (pintype "passive"))
    )
    (net (code "35") (name "C9") (class "Default")
      (node (ref "QB9") (pin "2") (pinfunction "S_2") (pintype "passive"))
      (node (ref "RCM9") (pin "1") (pinfunction "1_1") (pintype "passive"))
      (node (ref "RP10") (pin "1") (pinfunction "1_1") (pintype "passive"))
      (node (ref "X5") (pin "2") (pinfunction "2_2") (pintype "passive"))
      (node (ref "X6") (pin "5") (pinfunction "5_5") (pintype "passive"))
    )
    (net (code "36") (name "C9M") (class "Default")
      (node (ref "CCM10") (pin "2") (pinfunction "2_2") (pintype "passive"))
      (node (ref "CCM9") (pin "1") (pinfunction "1_1") (pintype "passive"))
      (node (ref "DCM10") (pin "A") (pinfunction "A_A") (pintype "passive"))
      (node (ref "DCM9") (pin "C") (pinfunction "C_C") (pintype "passive"))
      (node (ref "IC2") (pin "8") (pinfunction "C9_8") (pintype "bidirectional"))
      (node (ref "RCM9") (pin "2") (pinfunction "2_2") (pintype "passive"))
    )
    (net (code "37") (name "C10") (class "Default")
      (node (ref "QB10") (pin "2") (pinfunction "S_2") (pintype "passive"))
      (node (ref "RCM10") (pin "1") (pinfunction "1_1") (pintype "passive"))
      (node (ref "RP11") (pin "1") (pinfunction "1_1") (pintype "passive"))
      (node (ref "X3") (pin "2") (pinfunction "2_2") (pintype "passive"))
      (node (ref "X4") (pin "6") (pinfunction "6_6") (pintype "passive"))
    )
    (net (code "38") (name "C10M") (class "Default")
      (node (ref "CCM10") (pin "1") (pinfunction "1_1") (pintype "passive"))
      (node (ref "CCM11") (pin "2") (pinfunction "2_2") (pintype "passive"))
      (node (ref "DCM10") (pin "C") (pinfunction "C_C") (pintype "passive"))
      (node (ref "DCM11") (pin "A") (pinfunction "A_A") (pintype "passive"))
      (node (ref "IC2") (pin "6") (pinfunction "C10_6") (pintype "bidirectional"))
      (node (ref "RCM10") (pin "2") (pinfunction "2_2") (pintype "passive"))
    )
    (net (code "39") (name "C11") (class "Default")
      (node (ref "QB11") (pin "2") (pinfunction "S_2") (pintype "passive"))
      (node (ref "RCM11") (pin "1") (pinfunction "1_1") (pintype "passive"))
      (node (ref "RP12") (pin "1") (pinfunction "1_1") (pintype "passive"))
      (node (ref "X5") (pin "1") (pinfunction "1_1") (pintype "passive"))
      (node (ref "X6") (pin "6") (pinfunction "6_6") (pintype "passive"))
    )
    (net (code "40") (name "C11M") (class "Default")
      (node (ref "CCM11") (pin "1") (pinfunction "1_1") (pintype "passive"))
      (node (ref "CCM12") (pin "2") (pinfunction "2_2") (pintype "passive"))
      (node (ref "DCM11") (pin "C") (pinfunction "C_C") (pintype "passive"))
      (node (ref "DCM12") (pin "A") (pinfunction "A_A") (pintype "passive"))
      (node (ref "IC2") (pin "4") (pinfunction "C11_4") (pintype "bidirectional"))
      (node (ref "RCM11") (pin "2") (pinfunction "2_2") (pintype "passive"))
    )
    (net (code "41") (name "C12") (class "Default")
      (node (ref "L7") (pin "1") (pinfunction "1_1") (pintype "passive"))
      (node (ref "QB12") (pin "2") (pinfunction "S_2") (pintype "passive"))
      (node (ref "RCM12") (pin "1") (pinfunction "1_1") (pintype "passive"))
      (node (ref "X3") (pin "1") (pinfunction "1_1") (pintype "passive"))
      (node (ref "X4") (pin "7") (pinfunction "7_7") (pintype "passive"))
    )
    (net (code "42") (name "C12M") (class "Default")
      (node (ref "CCM12") (pin "1") (pinfunction "1_1") (pintype "passive"))
      (node (ref "DCM12") (pin "C") (pinfunction "C_C") (pintype "passive"))
      (node (ref "IC2") (pin "2") (pinfunction "C12_2") (pintype "bidirectional"))
      (node (ref "RCM12") (pin "2") (pinfunction "2_2") (pintype "passive"))
    )
    (net (code "43") (name "CANH") (class "Default")
      (node (ref "D3") (pin "2") (pinfunction "2_2") (pintype "passive"))
      (node (ref "L11") (pin "1") (pinfunction "3_1") (pintype "passive"))
      (node (ref "PL1") (pin "3") (pinfunction "3_3") (pintype "passive"))
      (node (ref "PL2") (pin "3") (pinfunction "3_3") (pintype "passive"))
    )
    (net (code "44") (name "CANL") (class "Default")
      (node (ref "D3") (pin "1") (pinfunction "1_1") (pintype "passive"))
      (node (ref "L11") (pin "2") (pinfunction "1_2") (pintype "passive"))
      (node (ref "PL1") (pin "4") (pinfunction "4_4") (pintype "passive"))
      (node (ref "PL2") (pin "4") (pinfunction "4_4") (pintype "passive"))
    )
    (net (code "45") (name "CANRX") (class "Default")
      (node (ref "R7") (pin "2") (pinfunction "2_2") (pintype "passive"))
      (node (ref "U$2") (pin "P$14") (pinfunction "O1_P$14") (pintype "bidirectional"))
    )
    (net (code "46") (name "CANTX") (class "Default")
      (node (ref "R6") (pin "2") (pinfunction "2_2") (pintype "passive"))
      (node (ref "U$2") (pin "P$13") (pinfunction "I2_P$13") (pintype "bidirectional"))
    )
    (net (code "47") (name "CAR+5V") (class "Default")
      (node (ref "C17") (pin "1") (pinfunction "1_1") (pintype "passive"))
      (node (ref "C6") (pin "1") (pinfunction "1_1") (pintype "passive"))
      (node (ref "C7") (pin "1") (pinfunction "1_1") (pintype "passive"))
      (node (ref "IC5") (pin "3") (pinfunction "VDD_3") (pintype "bidirectional"))
      (node (ref "JP1") (pin "1") (pinfunction "1_1") (pintype "passive"))
      (node (ref "REG5_C3") (pin "1") (pinfunction "1_1") (pintype "passive"))
      (node (ref "REG5_D1") (pin "2") (pinfunction "A_2") (pintype "passive"))
      (node (ref "REG5_L") (pin "2") (pinfunction "2_2") (pintype "passive"))
      (node (ref "REG5_R2") (pin "2") (pinfunction "2_2") (pintype "passive"))
      (node (ref "U$2") (pin "P$1") (pinfunction "VDD_P$1") (pintype "bidirectional"))
      (node (ref "U$2") (pin "P$6") (pinfunction "RCSEL_P$6") (pintype "bidirectional"))
      (node (ref "U$2") (pin "P$7") (pinfunction "EN1_P$7") (pintype "bidirectional"))
    )
    (net (code "48") (name "CARGND") (class "Default")
      (node (ref "C17") (pin "2") (pinfunction "2_2") (pintype "passive"))
      (node (ref "C6") (pin "2") (pinfunction "2_2") (pintype "passive"))
      (node (ref "C7") (pin "2") (pinfunction "2_2") (pintype "passive"))
      (node (ref "D3") (pin "3") (pinfunction "GND_3") (pintype "power_in"))
      (node (ref "D4") (pin "2") (pinfunction "A_2") (pintype "passive"))
      (node (ref "IC3") (pin "2") (pinfunction "GND_2") (pintype "bidirectional"))
      (node (ref "IC5") (pin "2") (pinfunction "VSS_2") (pintype "bidirectional"))
      (node (ref "PL1") (pin "5") (pinfunction "5_5") (pintype "passive"))
      (node (ref "PL1") (pin "6") (pinfunction "6_6") (pintype "passive"))
      (node (ref "PL2") (pin "5") (pinfunction "5_5") (pintype "passive"))
      (node (ref "PL2") (pin "6") (pinfunction "6_6") (pintype "passive"))
      (node (ref "R39") (pin "2") (pinfunction "2_2") (pintype "passive"))
      (node (ref "REG5_C1") (pin "2") (pinfunction "2_2") (pintype "passive"))
      (node (ref "REG5_C3") (pin "2") (pinfunction "2_2") (pintype "passive"))
      (node (ref "REG5_C4") (pin "2") (pinfunction "2_2") (pintype "passive"))
      (node (ref "REG5_D2") (pin "2") (pinfunction "A_2") (pintype "passive"))
      (node (ref "REG5_R1") (pin "1") (pinfunction "1_1") (pintype "passive"))
      (node (ref "U$2") (pin "P$2") (pinfunction "GND_P$2") (pintype "bidirectional"))
      (node (ref "U$2") (pin "P$5") (pinfunction "RCIN_P$5") (pintype "bidirectional"))
      (node (ref "U$2") (pin "P$8") (pinfunction "GND_P$8") (pintype "bidirectional"))
    )
    (net (code "49") (name "CARVIN") (class "Default")
      (node (ref "D4") (pin "1") (pinfunction "C_1") (pintype "passive"))
      (node (ref "L2") (pin "1") (pinfunction "1_1") (pintype "passive"))
      (node (ref "PL1") (pin "1") (pinfunction "1_1") (pintype "passive"))
      (node (ref "PL1") (pin "2") (pinfunction "2_2") (pintype "passive"))
      (node (ref "PL2") (pin "1") (pinfunction "1_1") (pintype "passive"))
      (node (ref "PL2") (pin "2") (pinfunction "2_2") (pintype "passive"))
      (node (ref "REG5_C4") (pin "1") (pinfunction "1_1") (pintype "passive"))
    )
    (net (code "50") (name "CSB") (class "Default")
      (node (ref "IC2") (pin "44") (pinfunction "CSBI_44") (pintype "bidirectional"))
      (node (ref "R1") (pin "2") (pinfunction "2_2") (pintype "passive"))
    )
    (net (code "51") (name "FSM") (class "Default")
      (node (ref "C2") (pin "1") (pinfunction "1_1") (pintype "passive"))
      (node (ref "CFSM") (pin "2") (pinfunction "2_2") (pintype "passive"))
      (node (ref "IC2") (pin "29") (pinfunction "VTEMP1_29") (pintype "bidirectional"))
      (node (ref "R59") (pin "1") (pinfunction "1_1") (pintype "passive"))
      (node (ref "R60") (pin "2") (pinfunction "2_2") (pintype "passive"))
    )
    (net (code "52") (name "GND") (class "Default")
      (node (ref "C1") (pin "2") (pinfunction "2_2") (pintype "passive"))
      (node (ref "C14") (pin "1") (pinfunction "1_1") (pintype "passive"))
      (node (ref "C15") (pin "1") (pinfunction "1_1") (pintype "passive"))
      (node (ref "C2") (pin "2") (pinfunction "2_2") (pintype "passive"))
      (node (ref "C22") (pin "2") (pinfunction "2_2") (pintype "passive"))
      (node (ref "C23") (pin "2") (pinfunction "2_2") (pintype "passive"))
      (node (ref "C27") (pin "2") (pinfunction "2_2") (pintype "passive"))
      (node (ref "C3") (pin "2") (pinfunction "2_2") (pintype "passive"))
      (node (ref "C34") (pin "2") (pinfunction "2_2") (pintype "passive"))
      (node (ref "C5") (pin "2") (pinfunction "2_2") (pintype "passive"))
      (node (ref "CFSM") (pin "1") (pinfunction "1_1") (pintype "passive"))
      (node (ref "CVREF") (pin "1") (pinfunction "1_1") (pintype "passive"))
      (node (ref "CVREG") (pin "1") (pinfunction "1_1") (pintype "passive"))
      (node (ref "D1") (pin "A") (pinfunction "A_A") (pintype "passive"))
      (node (ref "DT1") (pin "3") (pinfunction "C_3") (pintype "passive"))
      (node (ref "DT10") (pin "3") (pinfunction "C_3") (pintype "passive"))
      (node (ref "DT11") (pin "3") (pinfunction "C_3") (pintype "passive"))
      (node (ref "DT12") (pin "3") (pinfunction "C_3") (pintype "passive"))
      (node (ref "DT2") (pin "3") (pinfunction "C_3") (pintype "passive"))
      (node (ref "DT3") (pin "3") (pinfunction "C_3") (pintype "passive"))
      (node (ref "DT4") (pin "3") (pinfunction "C_3") (pintype "passive"))
      (node (ref "DT5") (pin "3") (pinfunction "C_3") (pintype "passive"))
      (node (ref "DT6") (pin "3") (pinfunction "C_3") (pintype "passive"))
      (node (ref "DT7") (pin "3") (pinfunction "C_3") (pintype "passive"))
      (node (ref "DT8") (pin "3") (pinfunction "C_3") (pintype "passive"))
      (node (ref "DT9") (pin "3") (pinfunction "C_3") (pintype "passive"))
      (node (ref "IC1") (pin "41") (pinfunction "VSS_41") (pintype "bidirectional"))
      (node (ref "IC1") (pin "5") (pinfunction "VSS_5") (pintype "bidirectional"))
      (node (ref "IC2") (pin "27") (pinfunction "V-_27") (pintype "bidirectional"))
      (node (ref "IC2") (pin "33") (pinfunction "TOS_33") (pintype "bidirectional"))
      (node (ref "IC2") (pin "34") (pinfunction "WDTB_34") (pintype "bidirectional"))
      (node (ref "IC2") (pin "35") (pinfunction "GPIO1_35") (pintype "bidirectional"))
      (node (ref "IC2") (pin "36") (pinfunction "GPIO2_36") (pintype "bidirectional"))
      (node (ref "IC2") (pin "37") (pinfunction "A0_37") (pintype "bidirectional"))
      (node (ref "IC2") (pin "38") (pinfunction "A1_38") (pintype "bidirectional"))
      (node (ref "IC2") (pin "39") (pinfunction "A2_39") (pintype "bidirectional"))
      (node (ref "IC2") (pin "40") (pinfunction "A3_40") (pintype "bidirectional"))
      (node (ref "J1") (pin "6") (pinfunction "6_6") (pintype "passive"))
      (node (ref "NTC_C1") (pin "2") (pinfunction "2_2") (pintype "passive"))
      (node (ref "NTC_C2") (pin "2") (pinfunction "2_2") (pintype "passive"))
      (node (ref "NTC_C3") (pin "2") (pinfunction "2_2") (pintype "passive"))
      (node (ref "NTC_C4") (pin "2") (pinfunction "2_2") (pintype "passive"))
      (node (ref "Q2") (pin "2") (pinfunction "S_2") (pintype "passive"))
      (node (ref "R11") (pin "1") (pinfunction "1_1") (pintype "passive"))
      (node (ref "R60") (pin "1") (pinfunction "1_1") (pintype "passive"))
      (node (ref "RGQ1_3") (pin "1") (pinfunction "1_1") (pintype "passive"))
      (node (ref "U$2") (pin "P$11") (pinfunction "VSEL_P$11") (pintype "bidirectional"))
      (node (ref "U$2") (pin "P$15") (pinfunction "GNDISO_P$15") (pintype "bidirectional"))
      (node (ref "U$2") (pin "P$9") (pinfunction "GNDISO_P$9") (pintype "bidirectional"))
      (node (ref "V-R") (pin "2") (pinfunction "2_2") (pintype "passive"))
      (node (ref "X1") (pin "3") (pinfunction "3_3") (pintype "passive"))
      (node (ref "X2") (pin "3") (pinfunction "3_3") (pintype "passive"))
    )
    (net (code "53") (name "ISP_CAN") (class "Default")
      (node (ref "IC1") (pin "14") (pinfunction "PIO0_3_14") (pintype "bidirectional"))
      (node (ref "R11") (pin "2") (pinfunction "2_2") (pintype "passive"))
    )
    (net (code "54") (name "ISP_ENTER") (class "Default")
      (node (ref "IC1") (pin "4") (pinfunction "PIO0_1/CLKOUT/CT32B0_MAT2_4") (pintype "bidirectional"))
      (node (ref "J1") (pin "5") (pinfunction "5_5") (pintype "passive"))
      (node (ref "R15") (pin "2") (pinfunction "2_2") (pintype "passive"))
    )
    (net (code "55") (name "LED1") (class "Default")
      (node (ref "IC1") (pin "23") (pinfunction "PIO0_7/~{CTS}_23") (pintype "bidirectional"))
      (node (ref "LED1") (pin "C") (pinfunction "C_C") (pintype "passive"))
    )
    (net (code "56") (name "LED2") (class "Default")
      (node (ref "IC1") (pin "24") (pinfunction "PIO2_9_24") (pintype "bidirectional"))
      (node (ref "LED2") (pin "C") (pinfunction "C_C") (pintype "passive"))
    )
    (net (code "57") (name "Net-(IC1-CANRX)") (class "Default")
      (node (ref "IC1") (pin "19") (pinfunction "CANRX_19") (pintype "bidirectional"))
      (node (ref "R7") (pin "1") (pinfunction "1_1") (pintype "passive"))
    )
    (net (code "58") (name "Net-(IC1-CANTX)") (class "Default")
      (node (ref "IC1") (pin "20") (pinfunction "CANTX_20") (pintype "bidirectional"))
      (node (ref "R6") (pin "1") (pinfunction "1_1") (pintype "passive"))
    )
    (net (code "59") (name "Net-(IC1-PIO2_0{slash}~{DTR}{slash}SSEL1)") (class "Default")
      (node (ref "IC1") (pin "2") (pinfunction "PIO2_0/~{DTR}/SSEL1_2") (pintype "bidirectional"))
      (node (ref "R1") (pin "1") (pinfunction "1_1") (pintype "passive"))
    )
    (net (code "60") (name "Net-(IC1-PIO2_1{slash}~{DSR}{slash}SCK1)") (class "Default")
      (node (ref "IC1") (pin "13") (pinfunction "PIO2_1/~{DSR}/SCK1_13") (pintype "bidirectional"))
      (node (ref "R3") (pin "1") (pinfunction "1_1") (pintype "passive"))
    )
    (net (code "61") (name "Net-(IC1-PIO2_2{slash}~{DCD}{slash}MISO1)") (class "Default")
      (node (ref "IC1") (pin "26") (pinfunction "PIO2_2/~{DCD}/MISO1_26") (pintype "bidirectional"))
      (node (ref "R4") (pin "1") (pinfunction "1_1") (pintype "passive"))
    )
    (net (code "62") (name "Net-(IC1-PIO2_3{slash}~{RI}{slash}MOSI1)") (class "Default")
      (node (ref "IC1") (pin "38") (pinfunction "PIO2_3/~{RI}/MOSI1_38") (pintype "bidirectional"))
      (node (ref "R5") (pin "1") (pinfunction "1_1") (pintype "passive"))
    )
    (net (code "63") (name "Net-(IC1-XTALIN)") (class "Default")
      (node (ref "C15") (pin "2") (pinfunction "2_2") (pintype "passive"))
      (node (ref "IC1") (pin "6") (pinfunction "XTALIN_6") (pintype "bidirectional"))
      (node (ref "Y1") (pin "2") (pinfunction "2_2") (pintype "passive"))
    )
    (net (code "64") (name "Net-(IC1-XTALOUT)") (class "Default")
      (node (ref "C14") (pin "2") (pinfunction "2_2") (pintype "passive"))
      (node (ref "IC1") (pin "7") (pinfunction "XTALOUT_7") (pintype "bidirectional"))
      (node (ref "Y1") (pin "1") (pinfunction "1_1") (pintype "passive"))
    )
    (net (code "65") (name "Net-(IC3-BOOST)") (class "Default")
      (node (ref "IC3") (pin "1") (pinfunction "BOOST_1") (pintype "bidirectional"))
      (node (ref "REG5_C2") (pin "1") (pinfunction "1_1") (pintype "passive"))
      (node (ref "REG5_D1") (pin "1") (pinfunction "C_1") (pintype "passive"))
    )
    (net (code "66") (name "Net-(IC3-FB)") (class "Default")
      (node (ref "IC3") (pin "3") (pinfunction "FB_3") (pintype "bidirectional"))
      (node (ref "REG5_R1") (pin "2") (pinfunction "2_2") (pintype "passive"))
      (node (ref "REG5_R2") (pin "1") (pinfunction "1_1") (pintype "passive"))
    )
    (net (code "67") (name "Net-(IC3-SW)") (class "Default")
      (node (ref "IC3") (pin "6") (pinfunction "SW_6") (pintype "bidirectional"))
      (node (ref "REG5_C2") (pin "2") (pinfunction "2_2") (pintype "passive"))
      (node (ref "REG5_D2") (pin "1") (pinfunction "C_1") (pintype "passive"))
      (node (ref "REG5_L") (pin "1") (pinfunction "1_1") (pintype "passive"))
    )
    (net (code "68") (name "Net-(IC3-VIN)") (class "Default")
      (node (ref "IC3") (pin "4") (pinfunction "~{SHDN}_4") (pintype "bidirectional"))
      (node (ref "IC3") (pin "5") (pinfunction "VIN_5") (pintype "bidirectional"))
      (node (ref "L2") (pin "2") (pinfunction "2_2") (pintype "passive"))
      (node (ref "REG5_C1") (pin "1") (pinfunction "1_1") (pintype "passive"))
    )
    (net (code "69") (name "Net-(IC5-CANH)") (class "Default")
      (node (ref "IC5") (pin "7") (pinfunction "CANH_7") (pintype "bidirectional"))
      (node (ref "L11") (pin "4") (pinfunction "4_4") (pintype "passive"))
    )
    (net (code "70") (name "Net-(IC5-CANL)") (class "Default")
      (node (ref "IC5") (pin "6") (pinfunction "CANL_6") (pintype "bidirectional"))
      (node (ref "L11") (pin "3") (pinfunction "2_3") (pintype "passive"))
    )
    (net (code "71") (name "Net-(IC5-RS)") (class "Default")
      (node (ref "IC5") (pin "8") (pinfunction "RS_8") (pintype "bidirectional"))
      (node (ref "R39") (pin "1") (pinfunction "1_1") (pintype "passive"))
    )
    (net (code "72") (name "Net-(IC5-RX)") (class "Default")
      (node (ref "IC5") (pin "4") (pinfunction "RX_4") (pintype "bidirectional"))
      (node (ref "R41") (pin "1") (pinfunction "1_1") (pintype "passive"))
    )
    (net (code "73") (name "Net-(IC5-TX)") (class "Default")
      (node (ref "IC5") (pin "1") (pinfunction "TX_1") (pintype "bidirectional"))
      (node (ref "R40") (pin "1") (pinfunction "1_1") (pintype "passive"))
    )
    (net (code "74") (name "Net-(L7-Pad2)") (class "Default")
      (node (ref "L7") (pin "2") (pinfunction "2_2") (pintype "passive"))
      (node (ref "V+R") (pin "1") (pinfunction "1_1") (pintype "passive"))
    )
    (net (code "75") (name "Net-(LED1-PadA)") (class "Default")
      (node (ref "LED1") (pin "A") (pinfunction "A_A") (pintype "passive"))
      (node (ref "R2") (pin "1") (pinfunction "1_1") (pintype "passive"))
    )
    (net (code "76") (name "Net-(LED2-PadA)") (class "Default")
      (node (ref "LED2") (pin "A") (pinfunction "A_A") (pintype "passive"))
      (node (ref "R8") (pin "1") (pinfunction "1_1") (pintype "passive"))
    )
    (net (code "77") (name "Net-(Q1-G)") (class "Default")
      (node (ref "D2") (pin "A") (pinfunction "A_A") (pintype "passive"))
      (node (ref "Q1") (pin "1") (pinfunction "G_1") (pintype "passive"))
      (node (ref "RGQ1_1") (pin "2") (pinfunction "2_2") (pintype "passive"))
      (node (ref "RGQ1_2") (pin "2") (pinfunction "2_2") (pintype "passive"))
    )
    (net (code "78") (name "Net-(Q1-S)") (class "Default")
      (node (ref "D1") (pin "C") (pinfunction "C_C") (pintype "passive"))
      (node (ref "D2") (pin "C") (pinfunction "C_C") (pintype "passive"))
      (node (ref "Q1") (pin "2") (pinfunction "S_2") (pintype "passive"))
      (node (ref "RGQ1_1") (pin "1") (pinfunction "1_1") (pintype "passive"))
      (node (ref "V+R") (pin "2") (pinfunction "2_2") (pintype "passive"))
    )
    (net (code "79") (name "Net-(Q2-D)") (class "Default")
      (node (ref "Q2") (pin "3") (pinfunction "D_3") (pintype "passive"))
      (node (ref "RGQ1_2") (pin "1") (pinfunction "1_1") (pintype "passive"))
    )
    (net (code "80") (name "Net-(QB1-D)") (class "Default")
      (node (ref "QB1") (pin "3") (pinfunction "D_3") (pintype "passive"))
      (node (ref "RP1") (pin "2") (pinfunction "2_2") (pintype "passive"))
    )
    (net (code "81") (name "Net-(QB1-G)") (class "Default")
      (node (ref "QB1") (pin "1") (pinfunction "G_1") (pintype "passive"))
      (node (ref "RBG1") (pin "1") (pinfunction "1_1") (pintype "passive"))
    )
    (net (code "82") (name "Net-(QB2-D)") (class "Default")
      (node (ref "QB2") (pin "3") (pinfunction "D_3") (pintype "passive"))
      (node (ref "RP2") (pin "2") (pinfunction "2_2") (pintype "passive"))
    )
    (net (code "83") (name "Net-(QB2-G)") (class "Default")
      (node (ref "QB2") (pin "1") (pinfunction "G_1") (pintype "passive"))
      (node (ref "RBG2") (pin "1") (pinfunction "1_1") (pintype "passive"))
    )
    (net (code "84") (name "Net-(QB3-D)") (class "Default")
      (node (ref "QB3") (pin "3") (pinfunction "D_3") (pintype "passive"))
      (node (ref "RP3") (pin "2") (pinfunction "2_2") (pintype "passive"))
    )
    (net (code "85") (name "Net-(QB3-G)") (class "Default")
      (node (ref "QB3") (pin "1") (pinfunction "G_1") (pintype "passive"))
      (node (ref "RBG3") (pin "1") (pinfunction "1_1") (pintype "passive"))
    )
    (net (code "86") (name "Net-(QB4-D)") (class "Default")
      (node (ref "QB4") (pin "3") (pinfunction "D_3") (pintype "passive"))
      (node (ref "RP4") (pin "2") (pinfunction "2_2") (pintype "passive"))
    )
    (net (code "87") (name "Net-(QB4-G)") (class "Default")
      (node (ref "QB4") (pin "1") (pinfunction "G_1") (pintype "passive"))
      (node (ref "RBG4") (pin "1") (pinfunction "1_1") (pintype "passive"))
    )
    (net (code "88") (name "Net-(QB5-D)") (class "Default")
      (node (ref "QB5") (pin "3") (pinfunction "D_3") (pintype "passive"))
      (node (ref "RP5") (pin "2") (pinfunction "2_2") (pintype "passive"))
    )
    (net (code "89") (name "Net-(QB5-G)") (class "Default")
      (node (ref "QB5") (pin "1") (pinfunction "G_1") (pintype "passive"))
      (node (ref "RBG5") (pin "1") (pinfunction "1_1") (pintype "passive"))
    )
    (net (code "90") (name "Net-(QB6-D)") (class "Default")
      (node (ref "QB6") (pin "3") (pinfunction "D_3") (pintype "passive"))
      (node (ref "RP6") (pin "2") (pinfunction "2_2") (pintype "passive"))
    )
    (net (code "91") (name "Net-(QB6-G)") (class "Default")
      (node (ref "QB6") (pin "1") (pinfunction "G_1") (pintype "passive"))
      (node (ref "RBG6") (pin "1") (pinfunction "1_1") (pintype "passive"))
    )
    (net (code "92") (name "Net-(QB7-D)") (class "Default")
      (node (ref "QB7") (pin "3") (pinfunction "D_3") (pintype "passive"))
      (node (ref "RP7") (pin "2") (pinfunction "2_2") (pintype "passive"))
    )
    (net (code "93") (name "Net-(QB7-G)") (class "Default")
      (node (ref "QB7") (pin "1") (pinfunction "G_1") (pintype "passive"))
      (node (ref "RBG7") (pin "1") (pinfunction "1_1") (pintype "passive"))
    )
    (net (code "94") (name "Net-(QB8-D)") (class "Default")
      (node (ref "QB8") (pin "3") (pinfunction "D_3") (pintype "passive"))
      (node (ref "RP8") (pin "2") (pinfunction "2_2") (pintype "passive"))
    )
    (net (code "95") (name "Net-(QB8-G)") (class "Default")
      (node (ref "QB8") (pin "1") (pinfunction "G_1") (pintype "passive"))
      (node (ref "RBG8") (pin "1") (pinfunction "1_1") (pintype "passive"))
    )
    (net (code "96") (name "Net-(QB9-D)") (class "Default")
      (node (ref "QB9") (pin "3") (pinfunction "D_3") (pintype "passive"))
      (node (ref "RP9") (pin "2") (pinfunction "2_2") (pintype "passive"))
    )
    (net (code "97") (name "Net-(QB9-G)") (class "Default")
      (node (ref "QB9") (pin "1") (pinfunction "G_1") (pintype "passive"))
      (node (ref "RBG9") (pin "1") (pinfunction "1_1") (pintype "passive"))
    )
    (net (code "98") (name "Net-(QB10-D)") (class "Default")
      (node (ref "QB10") (pin "3") (pinfunction "D_3") (pintype "passive"))
      (node (ref "RP10") (pin "2") (pinfunction "2_2") (pintype "passive"))
    )
    (net (code "99") (name "Net-(QB10-G)") (class "Default")
      (node (ref "QB10") (pin "1") (pinfunction "G_1") (pintype "passive"))
      (node (ref "RBG10") (pin "1") (pinfunction "1_1") (pintype "passive"))
    )
    (net (code "100") (name "Net-(QB11-D)") (class "Default")
      (node (ref "QB11") (pin "3") (pinfunction "D_3") (pintype "passive"))
      (node (ref "RP11") (pin "2") (pinfunction "2_2") (pintype "passive"))
    )
    (net (code "101") (name "Net-(QB11-G)") (class "Default")
      (node (ref "QB11") (pin "1") (pinfunction "G_1") (pintype "passive"))
      (node (ref "RBG11") (pin "1") (pinfunction "1_1") (pintype "passive"))
    )
    (net (code "102") (name "Net-(QB12-D)") (class "Default")
      (node (ref "QB12") (pin "3") (pinfunction "D_3") (pintype "passive"))
      (node (ref "RP12") (pin "2") (pinfunction "2_2") (pintype "passive"))
    )
    (net (code "103") (name "Net-(QB12-G)") (class "Default")
      (node (ref "QB12") (pin "1") (pinfunction "G_1") (pintype "passive"))
      (node (ref "RBG12") (pin "1") (pinfunction "1_1") (pintype "passive"))
    )
    (net (code "104") (name "Net-(U$2-I1)") (class "Default")
      (node (ref "R41") (pin "2") (pinfunction "2_2") (pintype "passive"))
      (node (ref "U$2") (pin "P$3") (pinfunction "I1_P$3") (pintype "bidirectional"))
    )
    (net (code "105") (name "Net-(U$2-O2)") (class "Default")
      (node (ref "R40") (pin "2") (pinfunction "2_2") (pintype "passive"))
      (node (ref "U$2") (pin "P$4") (pinfunction "O2_P$4") (pintype "bidirectional"))
    )
    (net (code "106") (name "RTEMP") (class "Default")
      (node (ref "C3") (pin "1") (pinfunction "1_1") (pintype "passive"))
      (node (ref "DT1") (pin "1") (pinfunction "A_1") (pintype "passive"))
      (node (ref "DT10") (pin "1") (pinfunction "A_1") (pintype "passive"))
      (node (ref "DT11") (pin "1") (pinfunction "A_1") (pintype "passive"))
      (node (ref "DT12") (pin "1") (pinfunction "A_1") (pintype "passive"))
      (node (ref "DT2") (pin "1") (pinfunction "A_1") (pintype "passive"))
      (node (ref "DT3") (pin "1") (pinfunction "A_1") (pintype "passive"))
      (node (ref "DT4") (pin "1") (pinfunction "A_1") (pintype "passive"))
      (node (ref "DT5") (pin "1") (pinfunction "A_1") (pintype "passive"))
      (node (ref "DT6") (pin "1") (pinfunction "A_1") (pintype "passive"))
      (node (ref "DT7") (pin "1") (pinfunction "A_1") (pintype "passive"))
      (node (ref "DT8") (pin "1") (pinfunction "A_1") (pintype "passive"))
      (node (ref "DT9") (pin "1") (pinfunction "A_1") (pintype "passive"))
      (node (ref "IC1") (pin "30") (pinfunction "PIO1_10/AD6/CT16B1_MAT1_30") (pintype "bidirectional"))
      (node (ref "R9") (pin "1") (pinfunction "1_1") (pintype "passive"))
    )
    (net (code "107") (name "SCK") (class "Default")
      (node (ref "IC2") (pin "41") (pinfunction "SCKI_41") (pintype "bidirectional"))
      (node (ref "R3") (pin "2") (pinfunction "2_2") (pintype "passive"))
    )
    (net (code "108") (name "SDI") (class "Default")
      (node (ref "IC2") (pin "42") (pinfunction "SDI_42") (pintype "bidirectional"))
      (node (ref "R5") (pin "2") (pinfunction "2_2") (pintype "passive"))
    )
    (net (code "109") (name "SDO") (class "Default")
      (node (ref "IC2") (pin "43") (pinfunction "SDO_43") (pintype "bidirectional"))
      (node (ref "R19") (pin "1") (pinfunction "1_1") (pintype "passive"))
      (node (ref "R4") (pin "2") (pinfunction "2_2") (pintype "passive"))
    )
    (net (code "110") (name "SWCLK") (class "Default")
      (node (ref "IC1") (pin "29") (pinfunction "PIO0_10/SWCLK/SCK0/CT16B0_MAT2_29") (pintype "bidirectional"))
      (node (ref "J1") (pin "4") (pinfunction "4_4") (pintype "passive"))
    )
    (net (code "111") (name "SWDIO") (class "Default")
      (node (ref "IC1") (pin "39") (pinfunction "PIO1_3/SWDIO/AD4/CT32B1_MAT2_39") (pintype "bidirectional"))
      (node (ref "J1") (pin "3") (pinfunction "3_3") (pintype "passive"))
    )
    (net (code "112") (name "V+") (class "Default")
      (node (ref "C1") (pin "1") (pinfunction "1_1") (pintype "passive"))
      (node (ref "IC2") (pin "1") (pinfunction "V+_1") (pintype "bidirectional"))
      (node (ref "Q1") (pin "3") (pinfunction "D_3") (pintype "passive"))
      (node (ref "R59") (pin "2") (pinfunction "2_2") (pintype "passive"))
    )
    (net (code "113") (name "VREF") (class "Default")
      (node (ref "CVREF") (pin "2") (pinfunction "2_2") (pintype "passive"))
      (node (ref "IC2") (pin "31") (pinfunction "VREF_31") (pintype "bidirectional"))
    )
    (net (code "114") (name "VREG") (class "Default")
      (node (ref "CVREG") (pin "2") (pinfunction "2_2") (pintype "passive"))
      (node (ref "IC2") (pin "32") (pinfunction "VREG_32") (pintype "bidirectional"))
    )
    (net (code "115") (name "unconnected-(IC1-PIO0_2{slash}SSEL{slash}CT16B0_CAP0-Pad10)") (class "Default")
      (node (ref "IC1") (pin "10") (pinfunction "PIO0_2/SSEL/CT16B0_CAP0_10") (pintype "bidirectional"))
    )
    (net (code "116") (name "unconnected-(IC1-PIO0_4{slash}SCL-Pad15)") (class "Default")
      (node (ref "IC1") (pin "15") (pinfunction "PIO0_4/SCL_15") (pintype "bidirectional"))
    )
    (net (code "117") (name "unconnected-(IC1-PIO0_5{slash}SDA-Pad16)") (class "Default")
      (node (ref "IC1") (pin "16") (pinfunction "PIO0_5/SDA_16") (pintype "bidirectional"))
    )
    (net (code "118") (name "unconnected-(IC1-PIO0_6{slash}SCK0-Pad22)") (class "Default")
      (node (ref "IC1") (pin "22") (pinfunction "PIO0_6/SCK0_22") (pintype "bidirectional"))
    )
    (net (code "119") (name "unconnected-(IC1-PIO0_8{slash}MISO0{slash}CT16B0_MAT0-Pad27)") (class "Default")
      (node (ref "IC1") (pin "27") (pinfunction "PIO0_8/MISO0/CT16B0_MAT0_27") (pintype "bidirectional"))
    )
    (net (code "120") (name "unconnected-(IC1-PIO0_9{slash}MOSI0{slash}CT16B0_MAT1-Pad28)") (class "Default")
      (node (ref "IC1") (pin "28") (pinfunction "PIO0_9/MOSI0/CT16B0_MAT1_28") (pintype "bidirectional"))
    )
    (net (code "121") (name "unconnected-(IC1-PIO1_4{slash}AD5{slash}CT32B1_MAT3-Pad40)") (class "Default")
      (node (ref "IC1") (pin "40") (pinfunction "PIO1_4/AD5/CT32B1_MAT3_40") (pintype "bidirectional"))
    )
    (net (code "122") (name "unconnected-(IC1-PIO1_5{slash}~{RTS}{slash}CT32B0_CAP0-Pad45)") (class "Default")
      (node (ref "IC1") (pin "45") (pinfunction "PIO1_5/~{RTS}/CT32B0_CAP0_45") (pintype "bidirectional"))
    )
    (net (code "123") (name "unconnected-(IC1-PIO1_6{slash}RXD{slash}CT32B0_MAT0-Pad46)") (class "Default")
      (node (ref "IC1") (pin "46") (pinfunction "PIO1_6/RXD/CT32B0_MAT0_46") (pintype "bidirectional"))
    )
    (net (code "124") (name "unconnected-(IC1-PIO1_7{slash}TXD{slash}CT32B0_MAT1-Pad47)") (class "Default")
      (node (ref "IC1") (pin "47") (pinfunction "PIO1_7/TXD/CT32B0_MAT1_47") (pintype "bidirectional"))
    )
    (net (code "125") (name "unconnected-(IC1-PIO1_8{slash}CT16B1_CAP0-Pad9)") (class "Default")
      (node (ref "IC1") (pin "9") (pinfunction "PIO1_8/CT16B1_CAP0_9") (pintype "bidirectional"))
    )
    (net (code "126") (name "unconnected-(IC1-PIO1_9{slash}CT16B1_MAT0-Pad17)") (class "Default")
      (node (ref "IC1") (pin "17") (pinfunction "PIO1_9/CT16B1_MAT0_17") (pintype "bidirectional"))
    )
    (net (code "127") (name "unconnected-(IC1-PIO1_11{slash}AD7-Pad42)") (class "Default")
      (node (ref "IC1") (pin "42") (pinfunction "PIO1_11/AD7_42") (pintype "bidirectional"))
    )
    (net (code "128") (name "unconnected-(IC1-PIO2_4-Pad18)") (class "Default")
      (node (ref "IC1") (pin "18") (pinfunction "PIO2_4_18") (pintype "bidirectional"))
    )
    (net (code "129") (name "unconnected-(IC1-PIO2_5-Pad21)") (class "Default")
      (node (ref "IC1") (pin "21") (pinfunction "PIO2_5_21") (pintype "bidirectional"))
    )
    (net (code "130") (name "unconnected-(IC1-PIO2_6-Pad1)") (class "Default")
      (node (ref "IC1") (pin "1") (pinfunction "PIO2_6_1") (pintype "bidirectional"))
    )
    (net (code "131") (name "unconnected-(IC1-PIO2_7-Pad11)") (class "Default")
      (node (ref "IC1") (pin "11") (pinfunction "PIO2_7_11") (pintype "bidirectional"))
    )
    (net (code "132") (name "unconnected-(IC1-PIO2_8-Pad12)") (class "Default")
      (node (ref "IC1") (pin "12") (pinfunction "PIO2_8_12") (pintype "bidirectional"))
    )
    (net (code "133") (name "unconnected-(IC1-PIO2_10-Pad25)") (class "Default")
      (node (ref "IC1") (pin "25") (pinfunction "PIO2_10_25") (pintype "bidirectional"))
    )
    (net (code "134") (name "unconnected-(IC1-PIO2_11{slash}SCK0-Pad31)") (class "Default")
      (node (ref "IC1") (pin "31") (pinfunction "PIO2_11/SCK0_31") (pintype "bidirectional"))
    )
    (net (code "135") (name "unconnected-(IC1-PIO3_0{slash}~{DTR}-Pad36)") (class "Default")
      (node (ref "IC1") (pin "36") (pinfunction "PIO3_0/~{DTR}_36") (pintype "bidirectional"))
    )
    (net (code "136") (name "unconnected-(IC1-PIO3_1{slash}~{DSR}-Pad37)") (class "Default")
      (node (ref "IC1") (pin "37") (pinfunction "PIO3_1/~{DSR}_37") (pintype "bidirectional"))
    )
    (net (code "137") (name "unconnected-(IC1-PIO3_2{slash}~{DCD}-Pad43)") (class "Default")
      (node (ref "IC1") (pin "43") (pinfunction "PIO3_2/~{DCD}_43") (pintype "bidirectional"))
    )
    (net (code "138") (name "unconnected-(IC1-PIO3_3{slash}~{RI}-Pad48)") (class "Default")
      (node (ref "IC1") (pin "48") (pinfunction "PIO3_3/~{RI}_48") (pintype "bidirectional"))
    )
    (net (code "139") (name "unconnected-(IC5-VRF-Pad5)") (class "Default")
      (node (ref "IC5") (pin "5") (pinfunction "VRF_5") (pintype "bidirectional"))
    )
    (net (code "140") (name "~{RESET}") (class "Default")
      (node (ref "C34") (pin "1") (pinfunction "1_1") (pintype "passive"))
      (node (ref "IC1") (pin "3") (pinfunction "PIO0_0/~{RESET}_3") (pintype "bidirectional"))
      (node (ref "J1") (pin "1") (pinfunction "1_1") (pintype "passive"))
      (node (ref "R52") (pin "2") (pinfunction "2_2") (pintype "passive"))
    )
  )
)
